# ESP32-C3_V1.net
KiCad netlist of a schematic drawn in Altium Designer
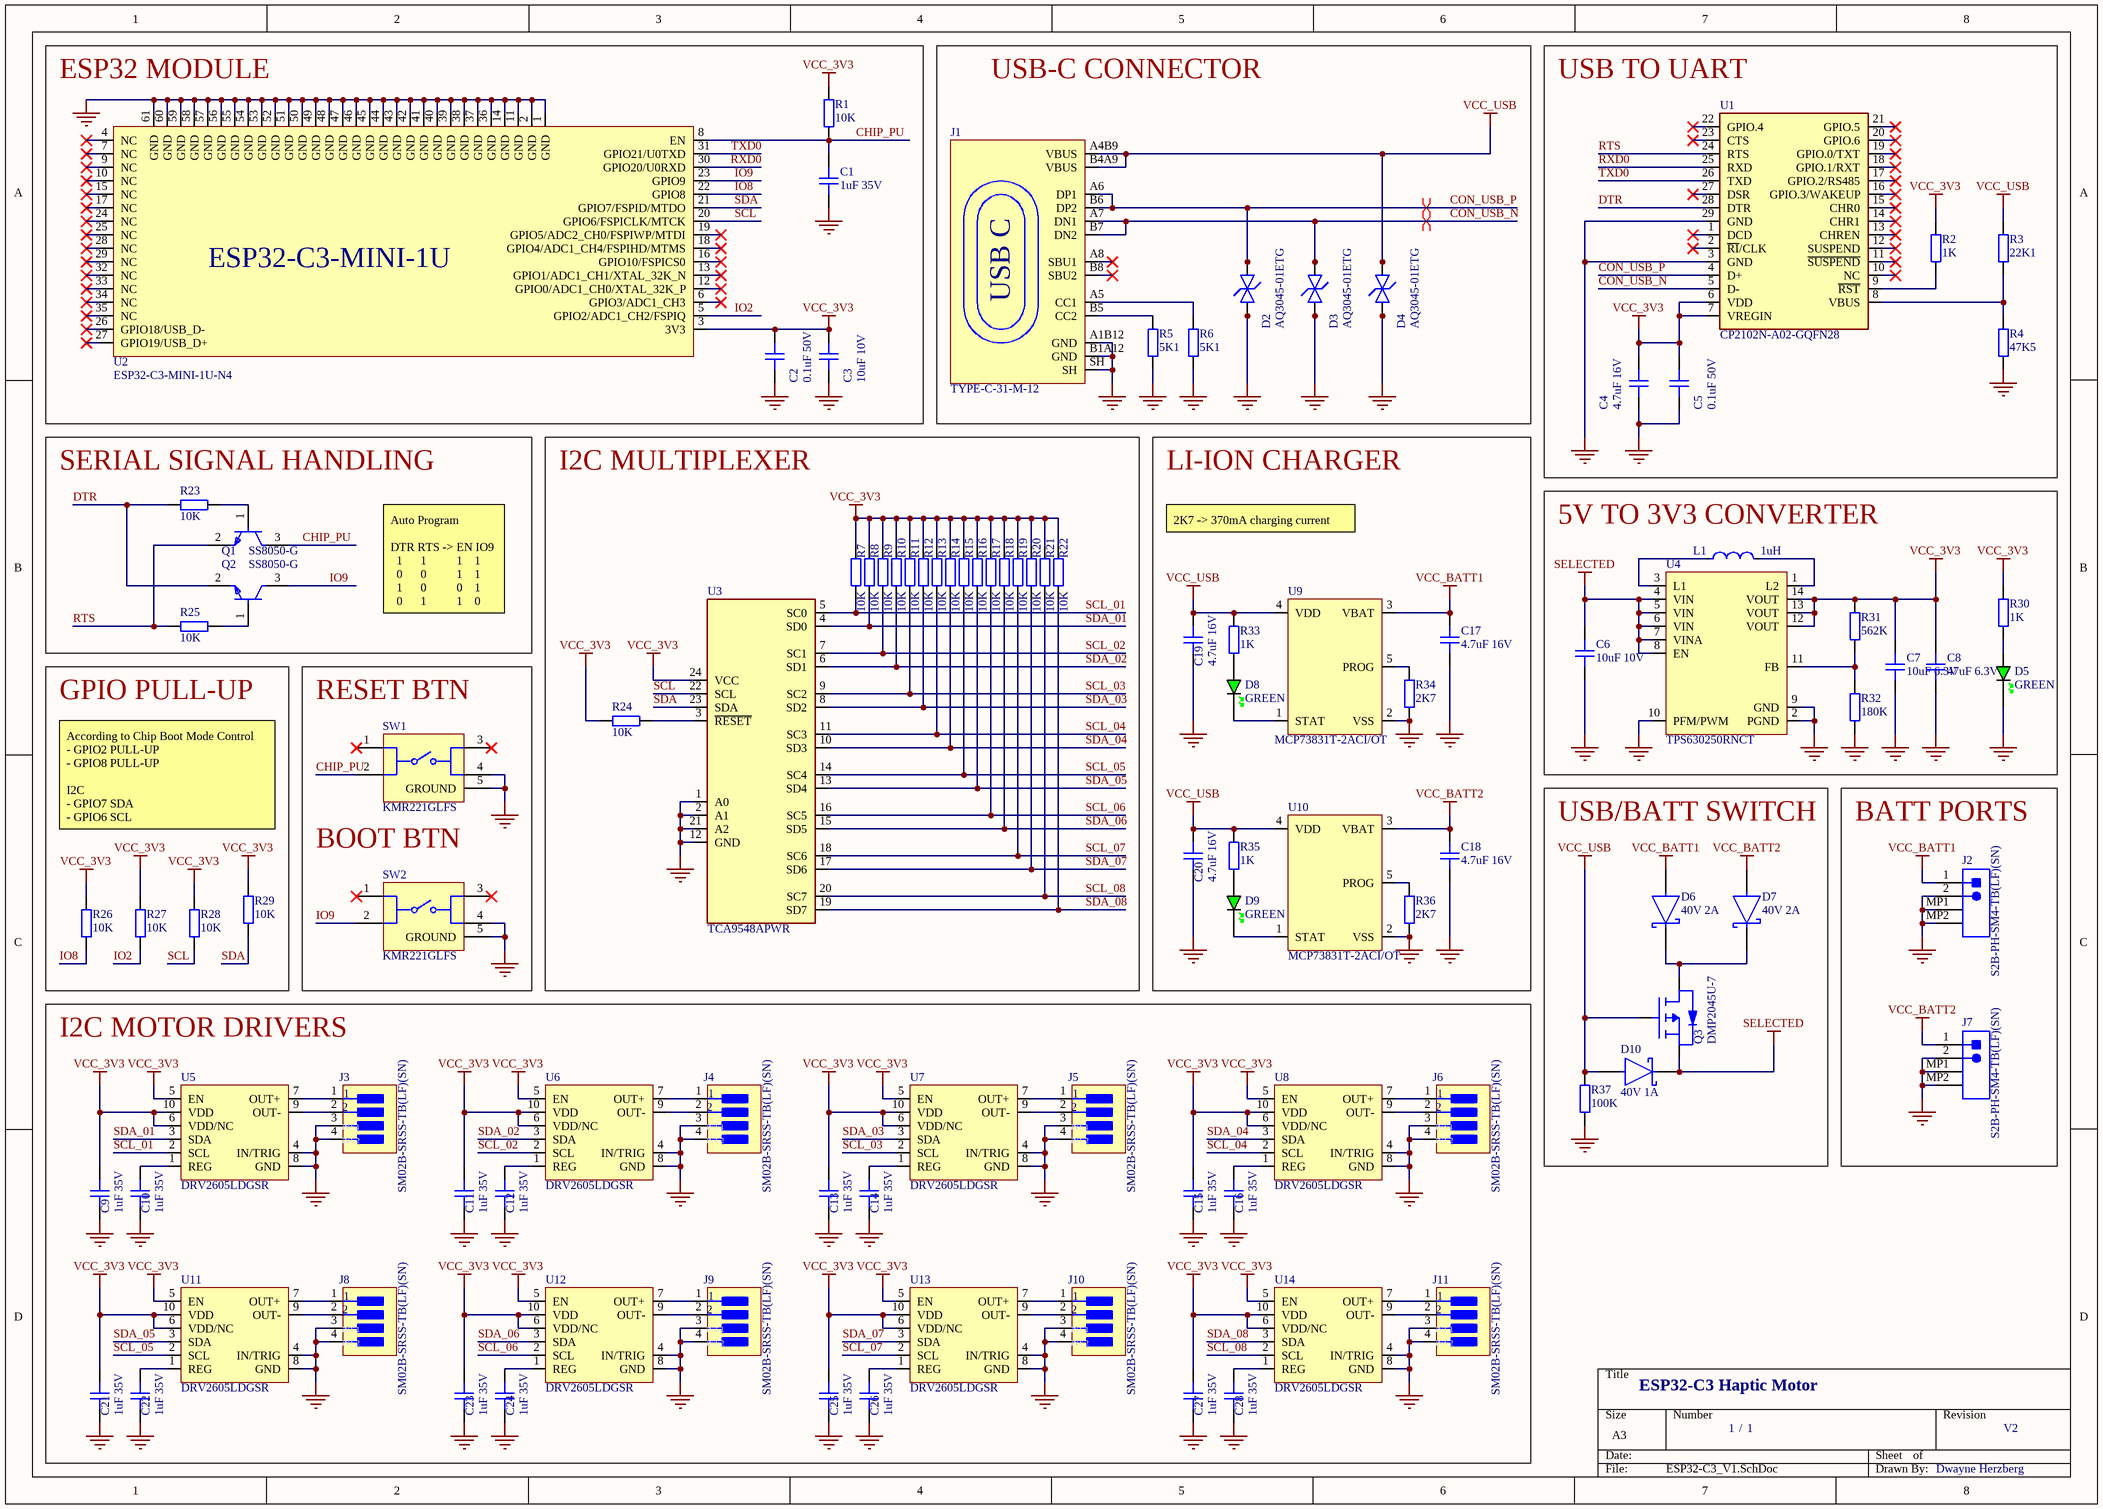
[diagram p0: ESP32-C3_V1.SchDoc]

(export (version "E")
  (design (tool "Eeschema 10.0.6"))
  (components
    (comp (ref "C1")
      (value "1uF 35V")
      (footprint "CAP_0402")
      (description "CAP CER 1UF 35V X5R 0402")
      (fields
        (field (name "MANUFACTURER") "Samsung")
        (field (name "MANUFACTURER PART NUMBER") "CL05A105KL5NRNC")
      )
      (libsource (lib "ESP32-C3") (part "CL05A105KL5NRNC"))
    )
    (comp (ref "C2")
      (value "0.1uF 50V")
      (footprint "CAP_0402")
      (description "CAP CER 0.1UF 50V X7R 0402")
      (fields
        (field (name "MANUFACTURER") "Samsung")
        (field (name "MANUFACTURER PART NUMBER") "CL05B104KB54PNC")
      )
      (libsource (lib "ESP32-C3") (part "CL05B104KB54PNC"))
    )
    (comp (ref "C3")
      (value "10uF 10V")
      (footprint "CAP_0402")
      (description "CAP CER 10UF 10V X5R 0402")
      (fields
        (field (name "MANUFACTURER") "Samsung")
        (field (name "MANUFACTURER PART NUMBER") "CL05A106MP8NUB8")
      )
      (libsource (lib "ESP32-C3") (part "CL05A106MP8NUB8"))
    )
    (comp (ref "C4")
      (value "4.7uF 16V")
      (footprint "CAP_0402")
      (description "CAP CER 4.7UF 16V X5R 0402")
      (fields
        (field (name "MANUFACTURER") "Samsung")
        (field (name "MANUFACTURER PART NUMBER") "CL05A475MO5NUNC")
      )
      (libsource (lib "ESP32-C3") (part "CL05A475MO5NUNC"))
    )
    (comp (ref "C5")
      (value "0.1uF 50V")
      (footprint "CAP_0402")
      (description "CAP CER 0.1UF 50V X7R 0402")
      (fields
        (field (name "MANUFACTURER") "Samsung")
        (field (name "MANUFACTURER PART NUMBER") "CL05B104KB54PNC")
      )
      (libsource (lib "ESP32-C3") (part "CL05B104KB54PNC"))
    )
    (comp (ref "C6")
      (value "10uF 10V")
      (footprint "CAP_0603")
      (description "CAP CER 10UF 10V X5R 0603")
      (fields
        (field (name "MANUFACTURER") "Samsung")
        (field (name "MANUFACTURER PART NUMBER") "CL10A106KP8NNNC")
      )
      (libsource (lib "ESP32-C3") (part "CL10A106KP8NNNC"))
    )
    (comp (ref "C7")
      (value "10uF 6.3V")
      (footprint "CAP_0603")
      (description "CAP CER 10UF 6.3V X5R 0603")
      (fields
        (field (name "MANUFACTURER") "Murata")
        (field (name "MANUFACTURER PART NUMBER") "GRM188R60J106ME47D")
      )
      (libsource (lib "ESP32-C3") (part "GRM188R60J106ME47D"))
    )
    (comp (ref "C8")
      (value "47uF 6.3V")
      (footprint "CAP_0805")
      (description "CAP CER 47UF 6.3V X5R 0805")
      (fields
        (field (name "MANUFACTURER") "Samsung")
        (field (name "MANUFACTURER PART NUMBER") "CL21A476MQYNNNE")
      )
      (libsource (lib "ESP32-C3") (part "CL21A476MQYNNNE"))
    )
    (comp (ref "C9")
      (value "1uF 35V")
      (footprint "CAP_0402")
      (description "CAP CER 1UF 35V X5R 0402")
      (fields
        (field (name "MANUFACTURER") "Samsung")
        (field (name "MANUFACTURER PART NUMBER") "CL05A105KL5NRNC")
      )
      (libsource (lib "ESP32-C3") (part "CL05A105KL5NRNC"))
    )
    (comp (ref "C10")
      (value "1uF 35V")
      (footprint "CAP_0402")
      (description "CAP CER 1UF 35V X5R 0402")
      (fields
        (field (name "MANUFACTURER") "Samsung")
        (field (name "MANUFACTURER PART NUMBER") "CL05A105KL5NRNC")
      )
      (libsource (lib "ESP32-C3") (part "CL05A105KL5NRNC"))
    )
    (comp (ref "C11")
      (value "1uF 35V")
      (footprint "CAP_0402")
      (description "CAP CER 1UF 35V X5R 0402")
      (fields
        (field (name "MANUFACTURER") "Samsung")
        (field (name "MANUFACTURER PART NUMBER") "CL05A105KL5NRNC")
      )
      (libsource (lib "ESP32-C3") (part "CL05A105KL5NRNC"))
    )
    (comp (ref "C12")
      (value "1uF 35V")
      (footprint "CAP_0402")
      (description "CAP CER 1UF 35V X5R 0402")
      (fields
        (field (name "MANUFACTURER") "Samsung")
        (field (name "MANUFACTURER PART NUMBER") "CL05A105KL5NRNC")
      )
      (libsource (lib "ESP32-C3") (part "CL05A105KL5NRNC"))
    )
    (comp (ref "C13")
      (value "1uF 35V")
      (footprint "CAP_0402")
      (description "CAP CER 1UF 35V X5R 0402")
      (fields
        (field (name "MANUFACTURER") "Samsung")
        (field (name "MANUFACTURER PART NUMBER") "CL05A105KL5NRNC")
      )
      (libsource (lib "ESP32-C3") (part "CL05A105KL5NRNC"))
    )
    (comp (ref "C14")
      (value "1uF 35V")
      (footprint "CAP_0402")
      (description "CAP CER 1UF 35V X5R 0402")
      (fields
        (field (name "MANUFACTURER") "Samsung")
        (field (name "MANUFACTURER PART NUMBER") "CL05A105KL5NRNC")
      )
      (libsource (lib "ESP32-C3") (part "CL05A105KL5NRNC"))
    )
    (comp (ref "C15")
      (value "1uF 35V")
      (footprint "CAP_0402")
      (description "CAP CER 1UF 35V X5R 0402")
      (fields
        (field (name "MANUFACTURER") "Samsung")
        (field (name "MANUFACTURER PART NUMBER") "CL05A105KL5NRNC")
      )
      (libsource (lib "ESP32-C3") (part "CL05A105KL5NRNC"))
    )
    (comp (ref "C16")
      (value "1uF 35V")
      (footprint "CAP_0402")
      (description "CAP CER 1UF 35V X5R 0402")
      (fields
        (field (name "MANUFACTURER") "Samsung")
        (field (name "MANUFACTURER PART NUMBER") "CL05A105KL5NRNC")
      )
      (libsource (lib "ESP32-C3") (part "CL05A105KL5NRNC"))
    )
    (comp (ref "C17")
      (value "4.7uF 16V")
      (footprint "CAP_0402")
      (description "CAP CER 4.7UF 16V X5R 0402")
      (fields
        (field (name "MANUFACTURER") "Samsung")
        (field (name "MANUFACTURER PART NUMBER") "CL05A475MO5NUNC")
      )
      (libsource (lib "ESP32-C3") (part "CL05A475MO5NUNC"))
    )
    (comp (ref "C18")
      (value "4.7uF 16V")
      (footprint "CAP_0402")
      (description "CAP CER 4.7UF 16V X5R 0402")
      (fields
        (field (name "MANUFACTURER") "Samsung")
        (field (name "MANUFACTURER PART NUMBER") "CL05A475MO5NUNC")
      )
      (libsource (lib "ESP32-C3") (part "CL05A475MO5NUNC"))
    )
    (comp (ref "C19")
      (value "4.7uF 16V")
      (footprint "CAP_0402")
      (description "CAP CER 4.7UF 16V X5R 0402")
      (fields
        (field (name "MANUFACTURER") "Samsung")
        (field (name "MANUFACTURER PART NUMBER") "CL05A475MO5NUNC")
      )
      (libsource (lib "ESP32-C3") (part "CL05A475MO5NUNC"))
    )
    (comp (ref "C20")
      (value "4.7uF 16V")
      (footprint "CAP_0402")
      (description "CAP CER 4.7UF 16V X5R 0402")
      (fields
        (field (name "MANUFACTURER") "Samsung")
        (field (name "MANUFACTURER PART NUMBER") "CL05A475MO5NUNC")
      )
      (libsource (lib "ESP32-C3") (part "CL05A475MO5NUNC"))
    )
    (comp (ref "C21")
      (value "1uF 35V")
      (footprint "CAP_0402")
      (description "CAP CER 1UF 35V X5R 0402")
      (fields
        (field (name "MANUFACTURER") "Samsung")
        (field (name "MANUFACTURER PART NUMBER") "CL05A105KL5NRNC")
      )
      (libsource (lib "ESP32-C3") (part "CL05A105KL5NRNC"))
    )
    (comp (ref "C22")
      (value "1uF 35V")
      (footprint "CAP_0402")
      (description "CAP CER 1UF 35V X5R 0402")
      (fields
        (field (name "MANUFACTURER") "Samsung")
        (field (name "MANUFACTURER PART NUMBER") "CL05A105KL5NRNC")
      )
      (libsource (lib "ESP32-C3") (part "CL05A105KL5NRNC"))
    )
    (comp (ref "C23")
      (value "1uF 35V")
      (footprint "CAP_0402")
      (description "CAP CER 1UF 35V X5R 0402")
      (fields
        (field (name "MANUFACTURER") "Samsung")
        (field (name "MANUFACTURER PART NUMBER") "CL05A105KL5NRNC")
      )
      (libsource (lib "ESP32-C3") (part "CL05A105KL5NRNC"))
    )
    (comp (ref "C24")
      (value "1uF 35V")
      (footprint "CAP_0402")
      (description "CAP CER 1UF 35V X5R 0402")
      (fields
        (field (name "MANUFACTURER") "Samsung")
        (field (name "MANUFACTURER PART NUMBER") "CL05A105KL5NRNC")
      )
      (libsource (lib "ESP32-C3") (part "CL05A105KL5NRNC"))
    )
    (comp (ref "C25")
      (value "1uF 35V")
      (footprint "CAP_0402")
      (description "CAP CER 1UF 35V X5R 0402")
      (fields
        (field (name "MANUFACTURER") "Samsung")
        (field (name "MANUFACTURER PART NUMBER") "CL05A105KL5NRNC")
      )
      (libsource (lib "ESP32-C3") (part "CL05A105KL5NRNC"))
    )
    (comp (ref "C26")
      (value "1uF 35V")
      (footprint "CAP_0402")
      (description "CAP CER 1UF 35V X5R 0402")
      (fields
        (field (name "MANUFACTURER") "Samsung")
        (field (name "MANUFACTURER PART NUMBER") "CL05A105KL5NRNC")
      )
      (libsource (lib "ESP32-C3") (part "CL05A105KL5NRNC"))
    )
    (comp (ref "C27")
      (value "1uF 35V")
      (footprint "CAP_0402")
      (description "CAP CER 1UF 35V X5R 0402")
      (fields
        (field (name "MANUFACTURER") "Samsung")
        (field (name "MANUFACTURER PART NUMBER") "CL05A105KL5NRNC")
      )
      (libsource (lib "ESP32-C3") (part "CL05A105KL5NRNC"))
    )
    (comp (ref "C28")
      (value "1uF 35V")
      (footprint "CAP_0402")
      (description "CAP CER 1UF 35V X5R 0402")
      (fields
        (field (name "MANUFACTURER") "Samsung")
        (field (name "MANUFACTURER PART NUMBER") "CL05A105KL5NRNC")
      )
      (libsource (lib "ESP32-C3") (part "CL05A105KL5NRNC"))
    )
    (comp (ref "D2")
      (value "AQ3045-01ETG")
      (footprint "SP353001ETG")
      (description "TVS DIODE 5.3VWM 12VC SOD882")
      (fields (field (name "MANUFACTURER") "Littelfuse") (field (name "JLCPCB PART") "C3710326"))
      (libsource (lib "ESP32-C3") (part "AQ3045-01ETG"))
    )
    (comp (ref "D3")
      (value "AQ3045-01ETG")
      (footprint "SP353001ETG")
      (description "TVS DIODE 5.3VWM 12VC SOD882")
      (fields (field (name "MANUFACTURER") "Littelfuse") (field (name "JLCPCB PART") "C3710326"))
      (libsource (lib "ESP32-C3") (part "AQ3045-01ETG"))
    )
    (comp (ref "D4")
      (value "AQ3045-01ETG")
      (footprint "SP353001ETG")
      (description "TVS DIODE 5.3VWM 12VC SOD882")
      (fields (field (name "MANUFACTURER") "Littelfuse") (field (name "JLCPCB PART") "C3710326"))
      (libsource (lib "ESP32-C3") (part "AQ3045-01ETG"))
    )
    (comp (ref "D5")
      (value "GREEN")
      (footprint "LED_0603_GREEN")
      (description "LED GREEN CLEAR 0603 SMD")
      (fields
        (field (name "MANUFACTURER") "Wurth Electronics")
        (field (name "MANUFACTURER PART NUMBER") "150060GS75000")
      )
      (libsource (lib "ESP32-C3") (part "150060GS75000"))
    )
    (comp (ref "D6")
      (value "40V 2A")
      (footprint "FP-DO-214AC-MFG")
      (description "DIODE SCHOTTKY 40V 2A DO214AC")
      (fields
        (field (name "MANUFACTURER") "Comchip")
        (field (name "MANUFACTURER PART NUMBER") "CDBA240LL-HF")
      )
      (libsource (lib "ESP32-C3") (part "CDBA240LL-HF"))
    )
    (comp (ref "D7")
      (value "40V 2A")
      (footprint "FP-DO-214AC-MFG")
      (description "DIODE SCHOTTKY 40V 2A DO214AC")
      (fields
        (field (name "MANUFACTURER") "Comchip")
        (field (name "MANUFACTURER PART NUMBER") "CDBA240LL-HF")
      )
      (libsource (lib "ESP32-C3") (part "CDBA240LL-HF"))
    )
    (comp (ref "D8")
      (value "GREEN")
      (footprint "LED_0603_GREEN")
      (description "LED GREEN CLEAR 0603 SMD")
      (fields
        (field (name "MANUFACTURER") "Wurth Electronics")
        (field (name "MANUFACTURER PART NUMBER") "150060GS75000")
      )
      (libsource (lib "ESP32-C3") (part "150060GS75000"))
    )
    (comp (ref "D9")
      (value "GREEN")
      (footprint "LED_0603_GREEN")
      (description "LED GREEN CLEAR 0603 SMD")
      (fields
        (field (name "MANUFACTURER") "Wurth Electronics")
        (field (name "MANUFACTURER PART NUMBER") "150060GS75000")
      )
      (libsource (lib "ESP32-C3") (part "150060GS75000"))
    )
    (comp (ref "D10")
      (value "40V 1A")
      (footprint "FP-SOD123-IPC_B")
      (description "DIODE SCHOTTKY 40V 1A SOD123")
      (fields (field (name "MANUFACTURER") "Diodes") (field (name "MANUFACTURER PART NUMBER") "1N5819HW-7-F"))
      (libsource (lib "ESP32-C3") (part "1N5819HW-7-F"))
    )
    (comp (ref "J1")
      (value "TYPE-C-31-M-12")
      (footprint "TYPE-C-31-M-12")
      (description "USB Type C Connector Horizontal SMT")
      (fields (field (name "MANUFACTURER") "Koren Hroparts") (field (name "JLCPCB PART") "C165948"))
      (libsource (lib "ESP32-C3") (part "TYPE-C-31-M-12"))
    )
    (comp (ref "J2")
      (value "S2B-PH-SM4-TB(LF)(SN)")
      (footprint "JST- S2B-PH-SM4-TB(LF)(SN)-2_V")
      (description "Male Header, Pitch 2 mm, 1 x 2 Position, Height 5.5 mm, -25 to 85 degC, RoHS, Tape and Reel")
      (fields (field (name "JLCPCB PART") "C295747"))
      (libsource (lib "ESP32-C3") (part "CMP-1755-00001-1"))
    )
    (comp (ref "J3")
      (value "SM02B-SRSS-TB(LF)(SN)")
      (footprint "FP-SM02B-SRSS-TB_LF_SN-MFG")
      (description "CONN HEADER SMD R/A 2POS 1MM")
      (fields (field (name "MANUFACTURER") "JST") (field (name "JLCPCB PART") "C160402"))
      (libsource (lib "ESP32-C3") (part "SM02B-SRSS-TB(LF)(SN)"))
    )
    (comp (ref "J4")
      (value "SM02B-SRSS-TB(LF)(SN)")
      (footprint "FP-SM02B-SRSS-TB_LF_SN-MFG")
      (description "CONN HEADER SMD R/A 2POS 1MM")
      (fields (field (name "MANUFACTURER") "JST") (field (name "JLCPCB PART") "C160402"))
      (libsource (lib "ESP32-C3") (part "SM02B-SRSS-TB(LF)(SN)"))
    )
    (comp (ref "J5")
      (value "SM02B-SRSS-TB(LF)(SN)")
      (footprint "FP-SM02B-SRSS-TB_LF_SN-MFG")
      (description "CONN HEADER SMD R/A 2POS 1MM")
      (fields (field (name "MANUFACTURER") "JST") (field (name "JLCPCB PART") "C160402"))
      (libsource (lib "ESP32-C3") (part "SM02B-SRSS-TB(LF)(SN)"))
    )
    (comp (ref "J6")
      (value "SM02B-SRSS-TB(LF)(SN)")
      (footprint "FP-SM02B-SRSS-TB_LF_SN-MFG")
      (description "CONN HEADER SMD R/A 2POS 1MM")
      (fields (field (name "MANUFACTURER") "JST") (field (name "JLCPCB PART") "C160402"))
      (libsource (lib "ESP32-C3") (part "SM02B-SRSS-TB(LF)(SN)"))
    )
    (comp (ref "J7")
      (value "S2B-PH-SM4-TB(LF)(SN)")
      (footprint "JST- S2B-PH-SM4-TB(LF)(SN)-2_V")
      (description "Male Header, Pitch 2 mm, 1 x 2 Position, Height 5.5 mm, -25 to 85 degC, RoHS, Tape and Reel")
      (fields (field (name "JLCPCB PART") "C295747"))
      (libsource (lib "ESP32-C3") (part "CMP-1755-00001-1"))
    )
    (comp (ref "J8")
      (value "SM02B-SRSS-TB(LF)(SN)")
      (footprint "FP-SM02B-SRSS-TB_LF_SN-MFG")
      (description "CONN HEADER SMD R/A 2POS 1MM")
      (fields (field (name "MANUFACTURER") "JST") (field (name "JLCPCB PART") "C160402"))
      (libsource (lib "ESP32-C3") (part "SM02B-SRSS-TB(LF)(SN)"))
    )
    (comp (ref "J9")
      (value "SM02B-SRSS-TB(LF)(SN)")
      (footprint "FP-SM02B-SRSS-TB_LF_SN-MFG")
      (description "CONN HEADER SMD R/A 2POS 1MM")
      (fields (field (name "MANUFACTURER") "JST") (field (name "JLCPCB PART") "C160402"))
      (libsource (lib "ESP32-C3") (part "SM02B-SRSS-TB(LF)(SN)"))
    )
    (comp (ref "J10")
      (value "SM02B-SRSS-TB(LF)(SN)")
      (footprint "FP-SM02B-SRSS-TB_LF_SN-MFG")
      (description "CONN HEADER SMD R/A 2POS 1MM")
      (fields (field (name "MANUFACTURER") "JST") (field (name "JLCPCB PART") "C160402"))
      (libsource (lib "ESP32-C3") (part "SM02B-SRSS-TB(LF)(SN)"))
    )
    (comp (ref "J11")
      (value "SM02B-SRSS-TB(LF)(SN)")
      (footprint "FP-SM02B-SRSS-TB_LF_SN-MFG")
      (description "CONN HEADER SMD R/A 2POS 1MM")
      (fields (field (name "MANUFACTURER") "JST") (field (name "JLCPCB PART") "C160402"))
      (libsource (lib "ESP32-C3") (part "SM02B-SRSS-TB(LF)(SN)"))
    )
    (comp (ref "L1")
      (value "1uH")
      (footprint "FP-XAL4020-102MEC-MFG")
      (description "FIXED IND 1UH 9.6A 14.6MOHM SM")
      (fields
        (field (name "MANUFACTURER") "Coilcraft")
        (field (name "MANUFACTURER PART NUMBER") "XAL4020-102MEC")
      )
      (libsource (lib "ESP32-C3") (part "XAL4020-102MEC"))
    )
    (comp (ref "Q1")
      (value "SS8050-G")
      (footprint "FP-SS8050-G-IPC_B")
      (description "TRANS NPN 25V 1.5A SOT-23-3")
      (fields (field (name "MANUFACTURER") "Comchip") (field (name "JLCPCB PART") "C3199946"))
      (libsource (lib "ESP32-C3") (part "SS8050-G"))
    )
    (comp (ref "Q2")
      (value "SS8050-G")
      (footprint "FP-SS8050-G-IPC_B")
      (description "TRANS NPN 25V 1.5A SOT-23-3")
      (fields (field (name "MANUFACTURER") "Comchip") (field (name "JLCPCB PART") "C3199946"))
      (libsource (lib "ESP32-C3") (part "SS8050-G"))
    )
    (comp (ref "Q3")
      (value "DMP2045U-7")
      (footprint "SOT96P240X115-3N")
      (description "MOSFET P-CH 20V 4.3A SOT23")
      (fields (field (name "MANUFACTURER") "Diodes") (field (name "JLCPCB PART") "C459541"))
      (libsource (lib "ESP32-C3") (part "DMP2045U-7"))
    )
    (comp (ref "R1")
      (value "10K")
      (footprint "RES_0402")
      (description "RES SMD 10K OHM 1% 1/16W 0402")
      (fields
        (field (name "MANUFACTURER") "Yageo")
        (field (name "MANUFACTURER PART NUMBER") "AC0402FR-0710KL")
      )
      (libsource (lib "ESP32-C3") (part "AC0402FR-0710KL"))
    )
    (comp (ref "R2")
      (value "1K")
      (footprint "RES_0402")
      (description "RES 1K OHM 5% 1/16W 0402")
      (fields
        (field (name "MANUFACTURER") "Yageo")
        (field (name "MANUFACTURER PART NUMBER") "RC0402JR-071KL")
      )
      (libsource (lib "ESP32-C3") (part "RC0402JR-071KL"))
    )
    (comp (ref "R3")
      (value "22K1")
      (footprint "RES_0402")
      (description "RES 22.1K OHM 1% 1/16W 0402")
      (fields
        (field (name "MANUFACTURER") "Yageo")
        (field (name "MANUFACTURER PART NUMBER") "RC0402FR-0722K1L")
      )
      (libsource (lib "ESP32-C3") (part "RC0402FR-0722K1L"))
    )
    (comp (ref "R4")
      (value "47K5")
      (footprint "RES_0402")
      (description "RES 47.5K OHM 1% 1/16W 0402")
      (fields
        (field (name "MANUFACTURER") "Yageo")
        (field (name "MANUFACTURER PART NUMBER") "RC0402FR-0747K5L")
      )
      (libsource (lib "ESP32-C3") (part "RC0402FR-0747K5L"))
    )
    (comp (ref "R5")
      (value "5K1")
      (footprint "RES_0402")
      (description "RES SMD 5.1K OHM 1% 1/16W 0402")
      (fields
        (field (name "MANUFACTURER") "Yageo")
        (field (name "MANUFACTURER PART NUMBER") "AC0402FR-075K1L")
      )
      (libsource (lib "ESP32-C3") (part "AC0402FR-075K1L"))
    )
    (comp (ref "R6")
      (value "5K1")
      (footprint "RES_0402")
      (description "RES SMD 5.1K OHM 1% 1/16W 0402")
      (fields
        (field (name "MANUFACTURER") "Yageo")
        (field (name "MANUFACTURER PART NUMBER") "AC0402FR-075K1L")
      )
      (libsource (lib "ESP32-C3") (part "AC0402FR-075K1L"))
    )
    (comp (ref "R7")
      (value "10K")
      (footprint "RES_0402")
      (description "RES SMD 10K OHM 1% 1/16W 0402")
      (fields
        (field (name "MANUFACTURER") "Yageo")
        (field (name "MANUFACTURER PART NUMBER") "AC0402FR-0710KL")
      )
      (libsource (lib "ESP32-C3") (part "AC0402FR-0710KL"))
    )
    (comp (ref "R8")
      (value "10K")
      (footprint "RES_0402")
      (description "RES SMD 10K OHM 1% 1/16W 0402")
      (fields
        (field (name "MANUFACTURER") "Yageo")
        (field (name "MANUFACTURER PART NUMBER") "AC0402FR-0710KL")
      )
      (libsource (lib "ESP32-C3") (part "AC0402FR-0710KL"))
    )
    (comp (ref "R9")
      (value "10K")
      (footprint "RES_0402")
      (description "RES SMD 10K OHM 1% 1/16W 0402")
      (fields
        (field (name "MANUFACTURER") "Yageo")
        (field (name "MANUFACTURER PART NUMBER") "AC0402FR-0710KL")
      )
      (libsource (lib "ESP32-C3") (part "AC0402FR-0710KL"))
    )
    (comp (ref "R10")
      (value "10K")
      (footprint "RES_0402")
      (description "RES SMD 10K OHM 1% 1/16W 0402")
      (fields
        (field (name "MANUFACTURER") "Yageo")
        (field (name "MANUFACTURER PART NUMBER") "AC0402FR-0710KL")
      )
      (libsource (lib "ESP32-C3") (part "AC0402FR-0710KL"))
    )
    (comp (ref "R11")
      (value "10K")
      (footprint "RES_0402")
      (description "RES SMD 10K OHM 1% 1/16W 0402")
      (fields
        (field (name "MANUFACTURER") "Yageo")
        (field (name "MANUFACTURER PART NUMBER") "AC0402FR-0710KL")
      )
      (libsource (lib "ESP32-C3") (part "AC0402FR-0710KL"))
    )
    (comp (ref "R12")
      (value "10K")
      (footprint "RES_0402")
      (description "RES SMD 10K OHM 1% 1/16W 0402")
      (fields
        (field (name "MANUFACTURER") "Yageo")
        (field (name "MANUFACTURER PART NUMBER") "AC0402FR-0710KL")
      )
      (libsource (lib "ESP32-C3") (part "AC0402FR-0710KL"))
    )
    (comp (ref "R13")
      (value "10K")
      (footprint "RES_0402")
      (description "RES SMD 10K OHM 1% 1/16W 0402")
      (fields
        (field (name "MANUFACTURER") "Yageo")
        (field (name "MANUFACTURER PART NUMBER") "AC0402FR-0710KL")
      )
      (libsource (lib "ESP32-C3") (part "AC0402FR-0710KL"))
    )
    (comp (ref "R14")
      (value "10K")
      (footprint "RES_0402")
      (description "RES SMD 10K OHM 1% 1/16W 0402")
      (fields
        (field (name "MANUFACTURER") "Yageo")
        (field (name "MANUFACTURER PART NUMBER") "AC0402FR-0710KL")
      )
      (libsource (lib "ESP32-C3") (part "AC0402FR-0710KL"))
    )
    (comp (ref "R15")
      (value "10K")
      (footprint "RES_0402")
      (description "RES SMD 10K OHM 1% 1/16W 0402")
      (fields
        (field (name "MANUFACTURER") "Yageo")
        (field (name "MANUFACTURER PART NUMBER") "AC0402FR-0710KL")
      )
      (libsource (lib "ESP32-C3") (part "AC0402FR-0710KL"))
    )
    (comp (ref "R16")
      (value "10K")
      (footprint "RES_0402")
      (description "RES SMD 10K OHM 1% 1/16W 0402")
      (fields
        (field (name "MANUFACTURER") "Yageo")
        (field (name "MANUFACTURER PART NUMBER") "AC0402FR-0710KL")
      )
      (libsource (lib "ESP32-C3") (part "AC0402FR-0710KL"))
    )
    (comp (ref "R17")
      (value "10K")
      (footprint "RES_0402")
      (description "RES SMD 10K OHM 1% 1/16W 0402")
      (fields
        (field (name "MANUFACTURER") "Yageo")
        (field (name "MANUFACTURER PART NUMBER") "AC0402FR-0710KL")
      )
      (libsource (lib "ESP32-C3") (part "AC0402FR-0710KL"))
    )
    (comp (ref "R18")
      (value "10K")
      (footprint "RES_0402")
      (description "RES SMD 10K OHM 1% 1/16W 0402")
      (fields
        (field (name "MANUFACTURER") "Yageo")
        (field (name "MANUFACTURER PART NUMBER") "AC0402FR-0710KL")
      )
      (libsource (lib "ESP32-C3") (part "AC0402FR-0710KL"))
    )
    (comp (ref "R19")
      (value "10K")
      (footprint "RES_0402")
      (description "RES SMD 10K OHM 1% 1/16W 0402")
      (fields
        (field (name "MANUFACTURER") "Yageo")
        (field (name "MANUFACTURER PART NUMBER") "AC0402FR-0710KL")
      )
      (libsource (lib "ESP32-C3") (part "AC0402FR-0710KL"))
    )
    (comp (ref "R20")
      (value "10K")
      (footprint "RES_0402")
      (description "RES SMD 10K OHM 1% 1/16W 0402")
      (fields
        (field (name "MANUFACTURER") "Yageo")
        (field (name "MANUFACTURER PART NUMBER") "AC0402FR-0710KL")
      )
      (libsource (lib "ESP32-C3") (part "AC0402FR-0710KL"))
    )
    (comp (ref "R21")
      (value "10K")
      (footprint "RES_0402")
      (description "RES SMD 10K OHM 1% 1/16W 0402")
      (fields
        (field (name "MANUFACTURER") "Yageo")
        (field (name "MANUFACTURER PART NUMBER") "AC0402FR-0710KL")
      )
      (libsource (lib "ESP32-C3") (part "AC0402FR-0710KL"))
    )
    (comp (ref "R22")
      (value "10K")
      (footprint "RES_0402")
      (description "RES SMD 10K OHM 1% 1/16W 0402")
      (fields
        (field (name "MANUFACTURER") "Yageo")
        (field (name "MANUFACTURER PART NUMBER") "AC0402FR-0710KL")
      )
      (libsource (lib "ESP32-C3") (part "AC0402FR-0710KL"))
    )
    (comp (ref "R23")
      (value "10K")
      (footprint "RES_0402")
      (description "RES SMD 10K OHM 1% 1/16W 0402")
      (fields
        (field (name "MANUFACTURER") "Yageo")
        (field (name "MANUFACTURER PART NUMBER") "AC0402FR-0710KL")
      )
      (libsource (lib "ESP32-C3") (part "AC0402FR-0710KL"))
    )
    (comp (ref "R24")
      (value "10K")
      (footprint "RES_0402")
      (description "RES SMD 10K OHM 1% 1/16W 0402")
      (fields
        (field (name "MANUFACTURER") "Yageo")
        (field (name "MANUFACTURER PART NUMBER") "AC0402FR-0710KL")
      )
      (libsource (lib "ESP32-C3") (part "AC0402FR-0710KL"))
    )
    (comp (ref "R25")
      (value "10K")
      (footprint "RES_0402")
      (description "RES SMD 10K OHM 1% 1/16W 0402")
      (fields
        (field (name "MANUFACTURER") "Yageo")
        (field (name "MANUFACTURER PART NUMBER") "AC0402FR-0710KL")
      )
      (libsource (lib "ESP32-C3") (part "AC0402FR-0710KL"))
    )
    (comp (ref "R26")
      (value "10K")
      (footprint "RES_0402")
      (description "RES SMD 10K OHM 1% 1/16W 0402")
      (fields
        (field (name "MANUFACTURER") "Yageo")
        (field (name "MANUFACTURER PART NUMBER") "AC0402FR-0710KL")
      )
      (libsource (lib "ESP32-C3") (part "AC0402FR-0710KL"))
    )
    (comp (ref "R27")
      (value "10K")
      (footprint "RES_0402")
      (description "RES SMD 10K OHM 1% 1/16W 0402")
      (fields
        (field (name "MANUFACTURER") "Yageo")
        (field (name "MANUFACTURER PART NUMBER") "AC0402FR-0710KL")
      )
      (libsource (lib "ESP32-C3") (part "AC0402FR-0710KL"))
    )
    (comp (ref "R28")
      (value "10K")
      (footprint "RES_0402")
      (description "RES SMD 10K OHM 1% 1/16W 0402")
      (fields
        (field (name "MANUFACTURER") "Yageo")
        (field (name "MANUFACTURER PART NUMBER") "AC0402FR-0710KL")
      )
      (libsource (lib "ESP32-C3") (part "AC0402FR-0710KL"))
    )
    (comp (ref "R29")
      (value "10K")
      (footprint "RES_0402")
      (description "RES SMD 10K OHM 1% 1/16W 0402")
      (fields
        (field (name "MANUFACTURER") "Yageo")
        (field (name "MANUFACTURER PART NUMBER") "AC0402FR-0710KL")
      )
      (libsource (lib "ESP32-C3") (part "AC0402FR-0710KL"))
    )
    (comp (ref "R30")
      (value "1K")
      (footprint "RES_0402")
      (description "RES 1K OHM 5% 1/16W 0402")
      (fields
        (field (name "MANUFACTURER") "Yageo")
        (field (name "MANUFACTURER PART NUMBER") "RC0402JR-071KL")
      )
      (libsource (lib "ESP32-C3") (part "RC0402JR-071KL"))
    )
    (comp (ref "R31")
      (value "562K")
      (footprint "RES_0603")
      (description "RES SMD 562K OHM 1% 1/10W 0603")
      (fields
        (field (name "MANUFACTURER") "Yageo")
        (field (name "MANUFACTURER PART NUMBER") "AC0603FR-07562KL")
      )
      (libsource (lib "ESP32-C3") (part "AC0603FR-07562KL"))
    )
    (comp (ref "R32")
      (value "180K")
      (footprint "RES_0603")
      (description "RES 180K OHM 1% 1/10W 0603")
      (fields
        (field (name "MANUFACTURER") "Yageo")
        (field (name "MANUFACTURER PART NUMBER") "RC0603FR-07180KL")
      )
      (libsource (lib "ESP32-C3") (part "RC0603FR-07180KL"))
    )
    (comp (ref "R33")
      (value "1K")
      (footprint "RES_0402")
      (description "RES 1K OHM 5% 1/16W 0402")
      (fields
        (field (name "MANUFACTURER") "Yageo")
        (field (name "MANUFACTURER PART NUMBER") "RC0402JR-071KL")
      )
      (libsource (lib "ESP32-C3") (part "RC0402JR-071KL"))
    )
    (comp (ref "R34")
      (value "2K7")
      (footprint "RES_0402")
      (description "RES 2.7K OHM 1% 1/16W 0402")
      (fields
        (field (name "MANUFACTURER") "Yageo")
        (field (name "MANUFACTURER PART NUMBER") "RC0402FR-072K7L")
      )
      (libsource (lib "ESP32-C3") (part "RC0402FR-072K7L"))
    )
    (comp (ref "R35")
      (value "1K")
      (footprint "RES_0402")
      (description "RES 1K OHM 5% 1/16W 0402")
      (fields
        (field (name "MANUFACTURER") "Yageo")
        (field (name "MANUFACTURER PART NUMBER") "RC0402JR-071KL")
      )
      (libsource (lib "ESP32-C3") (part "RC0402JR-071KL"))
    )
    (comp (ref "R36")
      (value "2K7")
      (footprint "RES_0402")
      (description "RES 2.7K OHM 1% 1/16W 0402")
      (fields
        (field (name "MANUFACTURER") "Yageo")
        (field (name "MANUFACTURER PART NUMBER") "RC0402FR-072K7L")
      )
      (libsource (lib "ESP32-C3") (part "RC0402FR-072K7L"))
    )
    (comp (ref "R37")
      (value "100K")
      (footprint "RES_0402")
      (description "RES 100K OHM 1% 1/16W 0402")
      (fields
        (field (name "MANUFACTURER") "Yageo")
        (field (name "MANUFACTURER PART NUMBER") "RC0402FR-07100KL")
      )
      (libsource (lib "ESP32-C3") (part "RC0402FR-07100KL"))
    )
    (comp (ref "SW1")
      (value "KMR221GLFS")
      (footprint "FP-KMR221GLFS-MFG")
      (description "SWITCH TACTILE SPST-NO 0.05A 32V")
      (fields (field (name "MANUFACTURER") "ITT C&K") (field (name "JLCPCB PART") "C72443"))
      (libsource (lib "ESP32-C3") (part "KMR221GLFS"))
    )
    (comp (ref "SW2")
      (value "KMR221GLFS")
      (footprint "FP-KMR221GLFS-MFG")
      (description "SWITCH TACTILE SPST-NO 0.05A 32V")
      (fields (field (name "MANUFACTURER") "ITT C&K") (field (name "JLCPCB PART") "C72443"))
      (libsource (lib "ESP32-C3") (part "KMR221GLFS"))
    )
    (comp (ref "U1")
      (value "CP2102N-A02-GQFN28")
      (footprint "FP-CP2102N-A02-GQFN28-IPC_B")
      (description "IC USB TO UART BRIDGE QFN28")
      (fields (field (name "MANUFACTURER") "Silicon Labs") (field (name "JLCPCB PART") "C1550553"))
      (libsource (lib "ESP32-C3") (part "CP2102N-A02-GQFN28"))
    )
    (comp (ref "U2")
      (value "ESP32-C3-MINI-1U-N4")
      (footprint "ESP32-C3-MINI-1U_EXP")
      (description "RF TXRX MOD BT WIFIU.FL SMD")
      (fields (field (name "MANUFACTURER") "Espressif Systems") (field (name "JLCPCB PART") "C2911374"))
      (libsource (lib "ESP32-C3") (part "ESP32-C3-MINI-1U-N4"))
    )
    (comp (ref "U3")
      (value "TCA9548APWR")
      (footprint "FP-PW0024A-IPC_B")
      (description "IC BUS SWITCH 1 X 8:1 24TSSOP")
      (fields (field (name "MANUFACTURER") "Texas Instruments") (field (name "JLCPCB PART") "C130026"))
      (libsource (lib "ESP32-C3") (part "TCA9548APWR"))
    )
    (comp (ref "U4")
      (value "TPS630250RNCT")
      (footprint "FP-RNC0014A-MFG")
      (description "IC REG BCK BST ADJ 2A/4A 14VQFN")
      (fields (field (name "MANUFACTURER") "Texas Instruments") (field (name "JLCPCB PART") "C2070882"))
      (libsource (lib "ESP32-C3") (part "TPS630250RNCT"))
    )
    (comp (ref "U5")
      (value "DRV2605LDGSR")
      (footprint "FP-DGS0010A-IPC_B")
      (description "IC MOTOR DRIVER 2V-5.5V 10VSSOP")
      (fields (field (name "MANUFACTURER") "Texas Instruments") (field (name "JLCPCB PART") "C527464"))
      (libsource (lib "ESP32-C3") (part "DRV2605LDGSR"))
    )
    (comp (ref "U6")
      (value "DRV2605LDGSR")
      (footprint "FP-DGS0010A-IPC_B")
      (description "IC MOTOR DRIVER 2V-5.5V 10VSSOP")
      (fields (field (name "MANUFACTURER") "Texas Instruments") (field (name "JLCPCB PART") "C527464"))
      (libsource (lib "ESP32-C3") (part "DRV2605LDGSR"))
    )
    (comp (ref "U7")
      (value "DRV2605LDGSR")
      (footprint "FP-DGS0010A-IPC_B")
      (description "IC MOTOR DRIVER 2V-5.5V 10VSSOP")
      (fields (field (name "MANUFACTURER") "Texas Instruments") (field (name "JLCPCB PART") "C527464"))
      (libsource (lib "ESP32-C3") (part "DRV2605LDGSR"))
    )
    (comp (ref "U8")
      (value "DRV2605LDGSR")
      (footprint "FP-DGS0010A-IPC_B")
      (description "IC MOTOR DRIVER 2V-5.5V 10VSSOP")
      (fields (field (name "MANUFACTURER") "Texas Instruments") (field (name "JLCPCB PART") "C527464"))
      (libsource (lib "ESP32-C3") (part "DRV2605LDGSR"))
    )
    (comp (ref "U9")
      (value "MCP73831T-2ACI/OT")
      (footprint "FP-C04-091-OT-IPC_B")
      (description "IC BATT CNTL LI-ION 1CEL SOT23-5")
      (fields (field (name "MANUFACTURER") "Microchip") (field (name "JLCPCB PART") "C424093"))
      (libsource (lib "ESP32-C3") (part "MCP73831T-2ACI/OT"))
    )
    (comp (ref "U10")
      (value "MCP73831T-2ACI/OT")
      (footprint "FP-C04-091-OT-IPC_B")
      (description "IC BATT CNTL LI-ION 1CEL SOT23-5")
      (fields (field (name "MANUFACTURER") "Microchip") (field (name "JLCPCB PART") "C424093"))
      (libsource (lib "ESP32-C3") (part "MCP73831T-2ACI/OT"))
    )
    (comp (ref "U11")
      (value "DRV2605LDGSR")
      (footprint "FP-DGS0010A-IPC_B")
      (description "IC MOTOR DRIVER 2V-5.5V 10VSSOP")
      (fields (field (name "MANUFACTURER") "Texas Instruments") (field (name "JLCPCB PART") "C527464"))
      (libsource (lib "ESP32-C3") (part "DRV2605LDGSR"))
    )
    (comp (ref "U12")
      (value "DRV2605LDGSR")
      (footprint "FP-DGS0010A-IPC_B")
      (description "IC MOTOR DRIVER 2V-5.5V 10VSSOP")
      (fields (field (name "MANUFACTURER") "Texas Instruments") (field (name "JLCPCB PART") "C527464"))
      (libsource (lib "ESP32-C3") (part "DRV2605LDGSR"))
    )
    (comp (ref "U13")
      (value "DRV2605LDGSR")
      (footprint "FP-DGS0010A-IPC_B")
      (description "IC MOTOR DRIVER 2V-5.5V 10VSSOP")
      (fields (field (name "MANUFACTURER") "Texas Instruments") (field (name "JLCPCB PART") "C527464"))
      (libsource (lib "ESP32-C3") (part "DRV2605LDGSR"))
    )
    (comp (ref "U14")
      (value "DRV2605LDGSR")
      (footprint "FP-DGS0010A-IPC_B")
      (description "IC MOTOR DRIVER 2V-5.5V 10VSSOP")
      (fields (field (name "MANUFACTURER") "Texas Instruments") (field (name "JLCPCB PART") "C527464"))
      (libsource (lib "ESP32-C3") (part "DRV2605LDGSR"))
    )
  )
  (nets
    (net (code "1") (name "/CHIP_PU") (class "Default")
      (node (ref "C1") (pin "2") (pinfunction "2_2") (pintype "passive"))
      (node (ref "Q1") (pin "3") (pinfunction "C_3") (pintype "passive"))
      (node (ref "R1") (pin "1") (pinfunction "1_1") (pintype "passive"))
      (node (ref "SW1") (pin "2") (pinfunction "2_2") (pintype "passive"))
      (node (ref "U2") (pin "8") (pinfunction "EN_8") (pintype "passive"))
    )
    (net (code "2") (name "/CON_USB_N") (class "Default")
      (node (ref "D3") (pin "2") (pinfunction "K_2") (pintype "passive"))
      (node (ref "D3") (pin "K") (pinfunction "K_K") (pintype "passive"))
      (node (ref "J1") (pin "A7") (pinfunction "DN1_A7") (pintype "passive"))
      (node (ref "J1") (pin "B7") (pinfunction "DN2_B7") (pintype "passive"))
      (node (ref "U1") (pin "5") (pinfunction "D-_5") (pintype "passive"))
    )
    (net (code "3") (name "/CON_USB_P") (class "Default")
      (node (ref "D2") (pin "2") (pinfunction "K_2") (pintype "passive"))
      (node (ref "D2") (pin "K") (pinfunction "K_K") (pintype "passive"))
      (node (ref "J1") (pin "A6") (pinfunction "DP1_A6") (pintype "passive"))
      (node (ref "J1") (pin "B6") (pinfunction "DP2_B6") (pintype "passive"))
      (node (ref "U1") (pin "4") (pinfunction "D+_4") (pintype "passive"))
    )
    (net (code "4") (name "/DTR") (class "Default")
      (node (ref "Q2") (pin "2") (pinfunction "E_2") (pintype "passive"))
      (node (ref "R23") (pin "2") (pinfunction "2_2") (pintype "passive"))
      (node (ref "U1") (pin "28") (pinfunction "DTR_28") (pintype "passive"))
    )
    (net (code "5") (name "/IO2") (class "Default")
      (node (ref "R27") (pin "1") (pinfunction "1_1") (pintype "passive"))
      (node (ref "U2") (pin "5") (pinfunction "GPIO2/ADC1_CH2/FSPIQ_5") (pintype "passive"))
    )
    (net (code "6") (name "/IO8") (class "Default")
      (node (ref "R26") (pin "1") (pinfunction "1_1") (pintype "passive"))
      (node (ref "U2") (pin "22") (pinfunction "GPIO8_22") (pintype "passive"))
    )
    (net (code "7") (name "/IO9") (class "Default")
      (node (ref "Q2") (pin "3") (pinfunction "C_3") (pintype "passive"))
      (node (ref "SW2") (pin "2") (pinfunction "2_2") (pintype "passive"))
      (node (ref "U2") (pin "23") (pinfunction "GPIO9_23") (pintype "passive"))
    )
    (net (code "8") (name "/RTS") (class "Default")
      (node (ref "Q1") (pin "2") (pinfunction "E_2") (pintype "passive"))
      (node (ref "R25") (pin "2") (pinfunction "2_2") (pintype "passive"))
      (node (ref "U1") (pin "24") (pinfunction "RTS_24") (pintype "passive"))
    )
    (net (code "9") (name "/RXD0") (class "Default")
      (node (ref "U1") (pin "25") (pinfunction "RXD_25") (pintype "passive"))
      (node (ref "U2") (pin "30") (pinfunction "GPIO20/U0RXD_30") (pintype "passive"))
    )
    (net (code "10") (name "/SCL") (class "Default")
      (node (ref "R28") (pin "1") (pinfunction "1_1") (pintype "passive"))
      (node (ref "U2") (pin "20") (pinfunction "GPIO6/FSPICLK/MTCK_20") (pintype "passive"))
      (node (ref "U3") (pin "22") (pinfunction "SCL_22") (pintype "passive"))
    )
    (net (code "11") (name "/SCL_01") (class "Default")
      (node (ref "R7") (pin "1") (pinfunction "1_1") (pintype "passive"))
      (node (ref "U3") (pin "5") (pinfunction "SC0_5") (pintype "passive"))
      (node (ref "U5") (pin "2") (pinfunction "SCL_2") (pintype "passive"))
    )
    (net (code "12") (name "/SCL_02") (class "Default")
      (node (ref "R9") (pin "1") (pinfunction "1_1") (pintype "passive"))
      (node (ref "U3") (pin "7") (pinfunction "SC1_7") (pintype "passive"))
      (node (ref "U6") (pin "2") (pinfunction "SCL_2") (pintype "passive"))
    )
    (net (code "13") (name "/SCL_03") (class "Default")
      (node (ref "R11") (pin "1") (pinfunction "1_1") (pintype "passive"))
      (node (ref "U3") (pin "9") (pinfunction "SC2_9") (pintype "passive"))
      (node (ref "U7") (pin "2") (pinfunction "SCL_2") (pintype "passive"))
    )
    (net (code "14") (name "/SCL_04") (class "Default")
      (node (ref "R13") (pin "1") (pinfunction "1_1") (pintype "passive"))
      (node (ref "U3") (pin "11") (pinfunction "SC3_11") (pintype "passive"))
      (node (ref "U8") (pin "2") (pinfunction "SCL_2") (pintype "passive"))
    )
    (net (code "15") (name "/SCL_05") (class "Default")
      (node (ref "R15") (pin "1") (pinfunction "1_1") (pintype "passive"))
      (node (ref "U11") (pin "2") (pinfunction "SCL_2") (pintype "passive"))
      (node (ref "U3") (pin "14") (pinfunction "SC4_14") (pintype "passive"))
    )
    (net (code "16") (name "/SCL_06") (class "Default")
      (node (ref "R17") (pin "1") (pinfunction "1_1") (pintype "passive"))
      (node (ref "U12") (pin "2") (pinfunction "SCL_2") (pintype "passive"))
      (node (ref "U3") (pin "16") (pinfunction "SC5_16") (pintype "passive"))
    )
    (net (code "17") (name "/SCL_07") (class "Default")
      (node (ref "R19") (pin "1") (pinfunction "1_1") (pintype "passive"))
      (node (ref "U13") (pin "2") (pinfunction "SCL_2") (pintype "passive"))
      (node (ref "U3") (pin "18") (pinfunction "SC6_18") (pintype "passive"))
    )
    (net (code "18") (name "/SCL_08") (class "Default")
      (node (ref "R21") (pin "1") (pinfunction "1_1") (pintype "passive"))
      (node (ref "U14") (pin "2") (pinfunction "SCL_2") (pintype "passive"))
      (node (ref "U3") (pin "20") (pinfunction "SC7_20") (pintype "passive"))
    )
    (net (code "19") (name "/SDA") (class "Default")
      (node (ref "R29") (pin "1") (pinfunction "1_1") (pintype "passive"))
      (node (ref "U2") (pin "21") (pinfunction "GPIO7/FSPID/MTDO_21") (pintype "passive"))
      (node (ref "U3") (pin "23") (pinfunction "SDA_23") (pintype "passive"))
    )
    (net (code "20") (name "/SDA_01") (class "Default")
      (node (ref "R8") (pin "1") (pinfunction "1_1") (pintype "passive"))
      (node (ref "U3") (pin "4") (pinfunction "SD0_4") (pintype "passive"))
      (node (ref "U5") (pin "3") (pinfunction "SDA_3") (pintype "passive"))
    )
    (net (code "21") (name "/SDA_02") (class "Default")
      (node (ref "R10") (pin "1") (pinfunction "1_1") (pintype "passive"))
      (node (ref "U3") (pin "6") (pinfunction "SD1_6") (pintype "passive"))
      (node (ref "U6") (pin "3") (pinfunction "SDA_3") (pintype "passive"))
    )
    (net (code "22") (name "/SDA_03") (class "Default")
      (node (ref "R12") (pin "1") (pinfunction "1_1") (pintype "passive"))
      (node (ref "U3") (pin "8") (pinfunction "SD2_8") (pintype "passive"))
      (node (ref "U7") (pin "3") (pinfunction "SDA_3") (pintype "passive"))
    )
    (net (code "23") (name "/SDA_04") (class "Default")
      (node (ref "R14") (pin "1") (pinfunction "1_1") (pintype "passive"))
      (node (ref "U3") (pin "10") (pinfunction "SD3_10") (pintype "passive"))
      (node (ref "U8") (pin "3") (pinfunction "SDA_3") (pintype "passive"))
    )
    (net (code "24") (name "/SDA_05") (class "Default")
      (node (ref "R16") (pin "1") (pinfunction "1_1") (pintype "passive"))
      (node (ref "U11") (pin "3") (pinfunction "SDA_3") (pintype "passive"))
      (node (ref "U3") (pin "13") (pinfunction "SD4_13") (pintype "passive"))
    )
    (net (code "25") (name "/SDA_06") (class "Default")
      (node (ref "R18") (pin "1") (pinfunction "1_1") (pintype "passive"))
      (node (ref "U12") (pin "3") (pinfunction "SDA_3") (pintype "passive"))
      (node (ref "U3") (pin "15") (pinfunction "SD5_15") (pintype "passive"))
    )
    (net (code "26") (name "/SDA_07") (class "Default")
      (node (ref "R20") (pin "1") (pinfunction "1_1") (pintype "passive"))
      (node (ref "U13") (pin "3") (pinfunction "SDA_3") (pintype "passive"))
      (node (ref "U3") (pin "17") (pinfunction "SD6_17") (pintype "passive"))
    )
    (net (code "27") (name "/SDA_08") (class "Default")
      (node (ref "R22") (pin "1") (pinfunction "1_1") (pintype "passive"))
      (node (ref "U14") (pin "3") (pinfunction "SDA_3") (pintype "passive"))
      (node (ref "U3") (pin "19") (pinfunction "SD7_19") (pintype "passive"))
    )
    (net (code "28") (name "/TXD0") (class "Default")
      (node (ref "U1") (pin "26") (pinfunction "TXD_26") (pintype "passive"))
      (node (ref "U2") (pin "31") (pinfunction "GPIO21/U0TXD_31") (pintype "passive"))
    )
    (net (code "29") (name "GND") (class "Default")
      (node (ref "C1") (pin "1") (pinfunction "1_1") (pintype "passive"))
      (node (ref "C10") (pin "1") (pinfunction "1_1") (pintype "passive"))
      (node (ref "C11") (pin "1") (pinfunction "1_1") (pintype "passive"))
      (node (ref "C12") (pin "1") (pinfunction "1_1") (pintype "passive"))
      (node (ref "C13") (pin "1") (pinfunction "1_1") (pintype "passive"))
      (node (ref "C14") (pin "1") (pinfunction "1_1") (pintype "passive"))
      (node (ref "C15") (pin "1") (pinfunction "1_1") (pintype "passive"))
      (node (ref "C16") (pin "1") (pinfunction "1_1") (pintype "passive"))
      (node (ref "C17") (pin "2") (pinfunction "2_2") (pintype "passive"))
      (node (ref "C18") (pin "2") (pinfunction "2_2") (pintype "passive"))
      (node (ref "C19") (pin "2") (pinfunction "2_2") (pintype "passive"))
      (node (ref "C2") (pin "1") (pinfunction "1_1") (pintype "passive"))
      (node (ref "C20") (pin "2") (pinfunction "2_2") (pintype "passive"))
      (node (ref "C21") (pin "1") (pinfunction "1_1") (pintype "passive"))
      (node (ref "C22") (pin "1") (pinfunction "1_1") (pintype "passive"))
      (node (ref "C23") (pin "1") (pinfunction "1_1") (pintype "passive"))
      (node (ref "C24") (pin "1") (pinfunction "1_1") (pintype "passive"))
      (node (ref "C25") (pin "1") (pinfunction "1_1") (pintype "passive"))
      (node (ref "C26") (pin "1") (pinfunction "1_1") (pintype "passive"))
      (node (ref "C27") (pin "1") (pinfunction "1_1") (pintype "passive"))
      (node (ref "C28") (pin "1") (pinfunction "1_1") (pintype "passive"))
      (node (ref "C3") (pin "1") (pinfunction "1_1") (pintype "passive"))
      (node (ref "C4") (pin "1") (pinfunction "1_1") (pintype "passive"))
      (node (ref "C5") (pin "1") (pinfunction "1_1") (pintype "passive"))
      (node (ref "C6") (pin "1") (pinfunction "1_1") (pintype "passive"))
      (node (ref "C7") (pin "1") (pinfunction "1_1") (pintype "passive"))
      (node (ref "C8") (pin "1") (pinfunction "1_1") (pintype "passive"))
      (node (ref "C9") (pin "1") (pinfunction "1_1") (pintype "passive"))
      (node (ref "D2") (pin "1") (pinfunction "A_1") (pintype "passive"))
      (node (ref "D2") (pin "A") (pinfunction "A_A") (pintype "passive"))
      (node (ref "D3") (pin "1") (pinfunction "A_1") (pintype "passive"))
      (node (ref "D3") (pin "A") (pinfunction "A_A") (pintype "passive"))
      (node (ref "D4") (pin "1") (pinfunction "A_1") (pintype "passive"))
      (node (ref "D4") (pin "A") (pinfunction "A_A") (pintype "passive"))
      (node (ref "D5") (pin "K") (pinfunction "K_K") (pintype "passive"))
      (node (ref "J1") (pin "A1B12") (pinfunction "GND_A1B12") (pintype "passive"))
      (node (ref "J1") (pin "B1A12") (pinfunction "GND_B1A12") (pintype "passive"))
      (node (ref "J1") (pin "SH") (pinfunction "SH_SH") (pintype "passive"))
      (node (ref "J10") (pin "3") (pinfunction "MNT_1_3") (pintype "passive"))
      (node (ref "J10") (pin "4") (pinfunction "MNT_2_4") (pintype "passive"))
      (node (ref "J11") (pin "3") (pinfunction "MNT_1_3") (pintype "passive"))
      (node (ref "J11") (pin "4") (pinfunction "MNT_2_4") (pintype "passive"))
      (node (ref "J2") (pin "2") (pinfunction "2_2") (pintype "passive"))
      (node (ref "J2") (pin "MP1") (pinfunction "MP1_MP1") (pintype "passive"))
      (node (ref "J2") (pin "MP2") (pinfunction "MP2_MP2") (pintype "passive"))
      (node (ref "J3") (pin "3") (pinfunction "MNT_1_3") (pintype "passive"))
      (node (ref "J3") (pin "4") (pinfunction "MNT_2_4") (pintype "passive"))
      (node (ref "J4") (pin "3") (pinfunction "MNT_1_3") (pintype "passive"))
      (node (ref "J4") (pin "4") (pinfunction "MNT_2_4") (pintype "passive"))
      (node (ref "J5") (pin "3") (pinfunction "MNT_1_3") (pintype "passive"))
      (node (ref "J5") (pin "4") (pinfunction "MNT_2_4") (pintype "passive"))
      (node (ref "J6") (pin "3") (pinfunction "MNT_1_3") (pintype "passive"))
      (node (ref "J6") (pin "4") (pinfunction "MNT_2_4") (pintype "passive"))
      (node (ref "J7") (pin "2") (pinfunction "2_2") (pintype "passive"))
      (node (ref "J7") (pin "MP1") (pinfunction "MP1_MP1") (pintype "passive"))
      (node (ref "J7") (pin "MP2") (pinfunction "MP2_MP2") (pintype "passive"))
      (node (ref "J8") (pin "3") (pinfunction "MNT_1_3") (pintype "passive"))
      (node (ref "J8") (pin "4") (pinfunction "MNT_2_4") (pintype "passive"))
      (node (ref "J9") (pin "3") (pinfunction "MNT_1_3") (pintype "passive"))
      (node (ref "J9") (pin "4") (pinfunction "MNT_2_4") (pintype "passive"))
      (node (ref "R32") (pin "1") (pinfunction "1_1") (pintype "passive"))
      (node (ref "R34") (pin "2") (pinfunction "2_2") (pintype "passive"))
      (node (ref "R36") (pin "2") (pinfunction "2_2") (pintype "passive"))
      (node (ref "R37") (pin "1") (pinfunction "1_1") (pintype "passive"))
      (node (ref "R4") (pin "1") (pinfunction "1_1") (pintype "passive"))
      (node (ref "R5") (pin "1") (pinfunction "1_1") (pintype "passive"))
      (node (ref "R6") (pin "1") (pinfunction "1_1") (pintype "passive"))
      (node (ref "SW1") (pin "4") (pinfunction "4_4") (pintype "passive"))
      (node (ref "SW1") (pin "5") (pinfunction "GROUND_5") (pintype "power_in"))
      (node (ref "SW2") (pin "4") (pinfunction "4_4") (pintype "passive"))
      (node (ref "SW2") (pin "5") (pinfunction "GROUND_5") (pintype "power_in"))
      (node (ref "U1") (pin "29") (pinfunction "GND_29") (pintype "passive"))
      (node (ref "U1") (pin "3") (pinfunction "GND_3") (pintype "passive"))
      (node (ref "U10") (pin "2") (pinfunction "VSS_2") (pintype "power_in"))
      (node (ref "U11") (pin "4") (pinfunction "IN/TRIG_4") (pintype "passive"))
      (node (ref "U11") (pin "8") (pinfunction "GND_8") (pintype "passive"))
      (node (ref "U12") (pin "4") (pinfunction "IN/TRIG_4") (pintype "passive"))
      (node (ref "U12") (pin "8") (pinfunction "GND_8") (pintype "passive"))
      (node (ref "U13") (pin "4") (pinfunction "IN/TRIG_4") (pintype "passive"))
      (node (ref "U13") (pin "8") (pinfunction "GND_8") (pintype "passive"))
      (node (ref "U14") (pin "4") (pinfunction "IN/TRIG_4") (pintype "passive"))
      (node (ref "U14") (pin "8") (pinfunction "GND_8") (pintype "passive"))
      (node (ref "U2") (pin "1") (pinfunction "GND_1") (pintype "passive"))
      (node (ref "U2") (pin "11") (pinfunction "GND_11") (pintype "passive"))
      (node (ref "U2") (pin "14") (pinfunction "GND_14") (pintype "passive"))
      (node (ref "U2") (pin "2") (pinfunction "GND_2") (pintype "passive"))
      (node (ref "U2") (pin "36") (pinfunction "GND_36") (pintype "passive"))
      (node (ref "U2") (pin "37") (pinfunction "GND_37") (pintype "passive"))
      (node (ref "U2") (pin "38") (pinfunction "GND_38") (pintype "passive"))
      (node (ref "U2") (pin "39") (pinfunction "GND_39") (pintype "passive"))
      (node (ref "U2") (pin "40") (pinfunction "GND_40") (pintype "passive"))
      (node (ref "U2") (pin "41") (pinfunction "GND_41") (pintype "passive"))
      (node (ref "U2") (pin "42") (pinfunction "GND_42") (pintype "passive"))
      (node (ref "U2") (pin "43") (pinfunction "GND_43") (pintype "passive"))
      (node (ref "U2") (pin "44") (pinfunction "GND_44") (pintype "passive"))
      (node (ref "U2") (pin "45") (pinfunction "GND_45") (pintype "passive"))
      (node (ref "U2") (pin "46") (pinfunction "GND_46") (pintype "passive"))
      (node (ref "U2") (pin "47") (pinfunction "GND_47") (pintype "passive"))
      (node (ref "U2") (pin "48") (pinfunction "GND_48") (pintype "passive"))
      (node (ref "U2") (pin "49") (pinfunction "GND_49") (pintype "passive"))
      (node (ref "U2") (pin "50") (pinfunction "GND_50") (pintype "passive"))
      (node (ref "U2") (pin "51") (pinfunction "GND_51") (pintype "passive"))
      (node (ref "U2") (pin "52") (pinfunction "GND_52") (pintype "passive"))
      (node (ref "U2") (pin "53") (pinfunction "GND_53") (pintype "passive"))
      (node (ref "U2") (pin "54") (pinfunction "GND_54") (pintype "passive"))
      (node (ref "U2") (pin "55") (pinfunction "GND_55") (pintype "passive"))
      (node (ref "U2") (pin "56") (pinfunction "GND_56") (pintype "passive"))
      (node (ref "U2") (pin "57") (pinfunction "GND_57") (pintype "passive"))
      (node (ref "U2") (pin "58") (pinfunction "GND_58") (pintype "passive"))
      (node (ref "U2") (pin "59") (pinfunction "GND_59") (pintype "passive"))
      (node (ref "U2") (pin "60") (pinfunction "GND_60") (pintype "passive"))
      (node (ref "U2") (pin "61") (pinfunction "GND_61") (pintype "passive"))
      (node (ref "U3") (pin "1") (pinfunction "A0_1") (pintype "passive"))
      (node (ref "U3") (pin "12") (pinfunction "GND_12") (pintype "passive"))
      (node (ref "U3") (pin "2") (pinfunction "A1_2") (pintype "passive"))
      (node (ref "U3") (pin "21") (pinfunction "A2_21") (pintype "passive"))
      (node (ref "U4") (pin "10") (pinfunction "PFM/PWM_10") (pintype "passive"))
      (node (ref "U4") (pin "2") (pinfunction "PGND_2") (pintype "passive"))
      (node (ref "U4") (pin "9") (pinfunction "GND_9") (pintype "passive"))
      (node (ref "U5") (pin "4") (pinfunction "IN/TRIG_4") (pintype "passive"))
      (node (ref "U5") (pin "8") (pinfunction "GND_8") (pintype "passive"))
      (node (ref "U6") (pin "4") (pinfunction "IN/TRIG_4") (pintype "passive"))
      (node (ref "U6") (pin "8") (pinfunction "GND_8") (pintype "passive"))
      (node (ref "U7") (pin "4") (pinfunction "IN/TRIG_4") (pintype "passive"))
      (node (ref "U7") (pin "8") (pinfunction "GND_8") (pintype "passive"))
      (node (ref "U8") (pin "4") (pinfunction "IN/TRIG_4") (pintype "passive"))
      (node (ref "U8") (pin "8") (pinfunction "GND_8") (pintype "passive"))
      (node (ref "U9") (pin "2") (pinfunction "VSS_2") (pintype "power_in"))
    )
    (net (code "30") (name "Net-(D5-PadA)") (class "Default")
      (node (ref "D5") (pin "A") (pinfunction "A_A") (pintype "passive"))
      (node (ref "R30") (pin "1") (pinfunction "1_1") (pintype "passive"))
    )
    (net (code "31") (name "Net-(D6-C)") (class "Default")
      (node (ref "D6") (pin "1") (pinfunction "C_1") (pintype "passive"))
      (node (ref "D7") (pin "1") (pinfunction "C_1") (pintype "passive"))
      (node (ref "Q3") (pin "3") (pinfunction "D_3") (pintype "passive"))
    )
    (net (code "32") (name "Net-(D8-PadA)") (class "Default")
      (node (ref "D8") (pin "A") (pinfunction "A_A") (pintype "passive"))
      (node (ref "R33") (pin "2") (pinfunction "2_2") (pintype "passive"))
    )
    (net (code "33") (name "Net-(D9-PadA)") (class "Default")
      (node (ref "D9") (pin "A") (pinfunction "A_A") (pintype "passive"))
      (node (ref "R35") (pin "2") (pinfunction "2_2") (pintype "passive"))
    )
    (net (code "34") (name "Net-(J1-CC1)") (class "Default")
      (node (ref "J1") (pin "A5") (pinfunction "CC1_A5") (pintype "passive"))
      (node (ref "R6") (pin "2") (pinfunction "2_2") (pintype "passive"))
    )
    (net (code "35") (name "Net-(J1-CC2)") (class "Default")
      (node (ref "J1") (pin "B5") (pinfunction "CC2_B5") (pintype "passive"))
      (node (ref "R5") (pin "2") (pinfunction "2_2") (pintype "passive"))
    )
    (net (code "36") (name "Net-(Q1-B)") (class "Default")
      (node (ref "Q1") (pin "1") (pinfunction "B_1") (pintype "passive"))
      (node (ref "R23") (pin "1") (pinfunction "1_1") (pintype "passive"))
    )
    (net (code "37") (name "Net-(Q2-B)") (class "Default")
      (node (ref "Q2") (pin "1") (pinfunction "B_1") (pintype "passive"))
      (node (ref "R25") (pin "1") (pinfunction "1_1") (pintype "passive"))
    )
    (net (code "38") (name "Net-(U1-VBUS)") (class "Default")
      (node (ref "R3") (pin "1") (pinfunction "1_1") (pintype "passive"))
      (node (ref "R4") (pin "2") (pinfunction "2_2") (pintype "passive"))
      (node (ref "U1") (pin "8") (pinfunction "VBUS_8") (pintype "passive"))
    )
    (net (code "39") (name "Net-(U1-~{RST})") (class "Default")
      (node (ref "R2") (pin "1") (pinfunction "1_1") (pintype "passive"))
      (node (ref "U1") (pin "9") (pinfunction "~{RST}_9") (pintype "passive"))
    )
    (net (code "40") (name "Net-(U3-~{RESET})") (class "Default")
      (node (ref "R24") (pin "1") (pinfunction "1_1") (pintype "passive"))
      (node (ref "U3") (pin "3") (pinfunction "~{RESET}_3") (pintype "passive"))
    )
    (net (code "41") (name "Net-(U4-FB)") (class "Default")
      (node (ref "R31") (pin "1") (pinfunction "1_1") (pintype "passive"))
      (node (ref "R32") (pin "2") (pinfunction "2_2") (pintype "passive"))
      (node (ref "U4") (pin "11") (pinfunction "FB_11") (pintype "passive"))
    )
    (net (code "42") (name "Net-(U4-L1)") (class "Default")
      (node (ref "L1") (pin "1") (pinfunction "1_1") (pintype "passive"))
      (node (ref "U4") (pin "3") (pinfunction "L1_3") (pintype "passive"))
    )
    (net (code "43") (name "Net-(U4-L2)") (class "Default")
      (node (ref "L1") (pin "2") (pinfunction "2_2") (pintype "passive"))
      (node (ref "U4") (pin "1") (pinfunction "L2_1") (pintype "passive"))
    )
    (net (code "44") (name "Net-(U5-OUT+)") (class "Default")
      (node (ref "J3") (pin "1") (pinfunction "1_1") (pintype "passive"))
      (node (ref "U5") (pin "7") (pinfunction "OUT+_7") (pintype "passive"))
    )
    (net (code "45") (name "Net-(U5-OUT-)") (class "Default")
      (node (ref "J3") (pin "2") (pinfunction "2_2") (pintype "passive"))
      (node (ref "U5") (pin "9") (pinfunction "OUT-_9") (pintype "passive"))
    )
    (net (code "46") (name "Net-(U5-REG)") (class "Default")
      (node (ref "C10") (pin "2") (pinfunction "2_2") (pintype "passive"))
      (node (ref "U5") (pin "1") (pinfunction "REG_1") (pintype "passive"))
    )
    (net (code "47") (name "Net-(U6-OUT+)") (class "Default")
      (node (ref "J4") (pin "1") (pinfunction "1_1") (pintype "passive"))
      (node (ref "U6") (pin "7") (pinfunction "OUT+_7") (pintype "passive"))
    )
    (net (code "48") (name "Net-(U6-OUT-)") (class "Default")
      (node (ref "J4") (pin "2") (pinfunction "2_2") (pintype "passive"))
      (node (ref "U6") (pin "9") (pinfunction "OUT-_9") (pintype "passive"))
    )
    (net (code "49") (name "Net-(U6-REG)") (class "Default")
      (node (ref "C12") (pin "2") (pinfunction "2_2") (pintype "passive"))
      (node (ref "U6") (pin "1") (pinfunction "REG_1") (pintype "passive"))
    )
    (net (code "50") (name "Net-(U7-OUT+)") (class "Default")
      (node (ref "J5") (pin "1") (pinfunction "1_1") (pintype "passive"))
      (node (ref "U7") (pin "7") (pinfunction "OUT+_7") (pintype "passive"))
    )
    (net (code "51") (name "Net-(U7-OUT-)") (class "Default")
      (node (ref "J5") (pin "2") (pinfunction "2_2") (pintype "passive"))
      (node (ref "U7") (pin "9") (pinfunction "OUT-_9") (pintype "passive"))
    )
    (net (code "52") (name "Net-(U7-REG)") (class "Default")
      (node (ref "C14") (pin "2") (pinfunction "2_2") (pintype "passive"))
      (node (ref "U7") (pin "1") (pinfunction "REG_1") (pintype "passive"))
    )
    (net (code "53") (name "Net-(U8-OUT+)") (class "Default")
      (node (ref "J6") (pin "1") (pinfunction "1_1") (pintype "passive"))
      (node (ref "U8") (pin "7") (pinfunction "OUT+_7") (pintype "passive"))
    )
    (net (code "54") (name "Net-(U8-OUT-)") (class "Default")
      (node (ref "J6") (pin "2") (pinfunction "2_2") (pintype "passive"))
      (node (ref "U8") (pin "9") (pinfunction "OUT-_9") (pintype "passive"))
    )
    (net (code "55") (name "Net-(U8-REG)") (class "Default")
      (node (ref "C16") (pin "2") (pinfunction "2_2") (pintype "passive"))
      (node (ref "U8") (pin "1") (pinfunction "REG_1") (pintype "passive"))
    )
    (net (code "56") (name "Net-(U9-PROG)") (class "Default")
      (node (ref "R34") (pin "1") (pinfunction "1_1") (pintype "passive"))
      (node (ref "U9") (pin "5") (pinfunction "PROG_5") (pintype "passive"))
    )
    (net (code "57") (name "Net-(U9-STAT)") (class "Default")
      (node (ref "D8") (pin "K") (pinfunction "K_K") (pintype "passive"))
      (node (ref "U9") (pin "1") (pinfunction "STAT_1") (pintype "passive"))
    )
    (net (code "58") (name "Net-(U10-PROG)") (class "Default")
      (node (ref "R36") (pin "1") (pinfunction "1_1") (pintype "passive"))
      (node (ref "U10") (pin "5") (pinfunction "PROG_5") (pintype "passive"))
    )
    (net (code "59") (name "Net-(U10-STAT)") (class "Default")
      (node (ref "D9") (pin "K") (pinfunction "K_K") (pintype "passive"))
      (node (ref "U10") (pin "1") (pinfunction "STAT_1") (pintype "passive"))
    )
    (net (code "60") (name "Net-(U11-OUT+)") (class "Default")
      (node (ref "J8") (pin "1") (pinfunction "1_1") (pintype "passive"))
      (node (ref "U11") (pin "7") (pinfunction "OUT+_7") (pintype "passive"))
    )
    (net (code "61") (name "Net-(U11-OUT-)") (class "Default")
      (node (ref "J8") (pin "2") (pinfunction "2_2") (pintype "passive"))
      (node (ref "U11") (pin "9") (pinfunction "OUT-_9") (pintype "passive"))
    )
    (net (code "62") (name "Net-(U11-REG)") (class "Default")
      (node (ref "C22") (pin "2") (pinfunction "2_2") (pintype "passive"))
      (node (ref "U11") (pin "1") (pinfunction "REG_1") (pintype "passive"))
    )
    (net (code "63") (name "Net-(U12-OUT+)") (class "Default")
      (node (ref "J9") (pin "1") (pinfunction "1_1") (pintype "passive"))
      (node (ref "U12") (pin "7") (pinfunction "OUT+_7") (pintype "passive"))
    )
    (net (code "64") (name "Net-(U12-OUT-)") (class "Default")
      (node (ref "J9") (pin "2") (pinfunction "2_2") (pintype "passive"))
      (node (ref "U12") (pin "9") (pinfunction "OUT-_9") (pintype "passive"))
    )
    (net (code "65") (name "Net-(U12-REG)") (class "Default")
      (node (ref "C24") (pin "2") (pinfunction "2_2") (pintype "passive"))
      (node (ref "U12") (pin "1") (pinfunction "REG_1") (pintype "passive"))
    )
    (net (code "66") (name "Net-(U13-OUT+)") (class "Default")
      (node (ref "J10") (pin "1") (pinfunction "1_1") (pintype "passive"))
      (node (ref "U13") (pin "7") (pinfunction "OUT+_7") (pintype "passive"))
    )
    (net (code "67") (name "Net-(U13-OUT-)") (class "Default")
      (node (ref "J10") (pin "2") (pinfunction "2_2") (pintype "passive"))
      (node (ref "U13") (pin "9") (pinfunction "OUT-_9") (pintype "passive"))
    )
    (net (code "68") (name "Net-(U13-REG)") (class "Default")
      (node (ref "C26") (pin "2") (pinfunction "2_2") (pintype "passive"))
      (node (ref "U13") (pin "1") (pinfunction "REG_1") (pintype "passive"))
    )
    (net (code "69") (name "Net-(U14-OUT+)") (class "Default")
      (node (ref "J11") (pin "1") (pinfunction "1_1") (pintype "passive"))
      (node (ref "U14") (pin "7") (pinfunction "OUT+_7") (pintype "passive"))
    )
    (net (code "70") (name "Net-(U14-OUT-)") (class "Default")
      (node (ref "J11") (pin "2") (pinfunction "2_2") (pintype "passive"))
      (node (ref "U14") (pin "9") (pinfunction "OUT-_9") (pintype "passive"))
    )
    (net (code "71") (name "Net-(U14-REG)") (class "Default")
      (node (ref "C28") (pin "2") (pinfunction "2_2") (pintype "passive"))
      (node (ref "U14") (pin "1") (pinfunction "REG_1") (pintype "passive"))
    )
    (net (code "72") (name "SELECTED") (class "Default")
      (node (ref "C6") (pin "2") (pinfunction "2_2") (pintype "passive"))
      (node (ref "D10") (pin "1") (pinfunction "C_1") (pintype "passive"))
      (node (ref "Q3") (pin "2") (pinfunction "S_2") (pintype "passive"))
      (node (ref "U4") (pin "4") (pinfunction "VIN_4") (pintype "passive"))
      (node (ref "U4") (pin "5") (pinfunction "VIN_5") (pintype "passive"))
      (node (ref "U4") (pin "6") (pinfunction "VIN_6") (pintype "passive"))
      (node (ref "U4") (pin "7") (pinfunction "VINA_7") (pintype "passive"))
      (node (ref "U4") (pin "8") (pinfunction "EN_8") (pintype "passive"))
    )
    (net (code "73") (name "VCC_3V3") (class "Default")
      (node (ref "C11") (pin "2") (pinfunction "2_2") (pintype "passive"))
      (node (ref "C13") (pin "2") (pinfunction "2_2") (pintype "passive"))
      (node (ref "C15") (pin "2") (pinfunction "2_2") (pintype "passive"))
      (node (ref "C2") (pin "2") (pinfunction "2_2") (pintype "passive"))
      (node (ref "C21") (pin "2") (pinfunction "2_2") (pintype "passive"))
      (node (ref "C23") (pin "2") (pinfunction "2_2") (pintype "passive"))
      (node (ref "C25") (pin "2") (pinfunction "2_2") (pintype "passive"))
      (node (ref "C27") (pin "2") (pinfunction "2_2") (pintype "passive"))
      (node (ref "C3") (pin "2") (pinfunction "2_2") (pintype "passive"))
      (node (ref "C4") (pin "2") (pinfunction "2_2") (pintype "passive"))
      (node (ref "C5") (pin "2") (pinfunction "2_2") (pintype "passive"))
      (node (ref "C7") (pin "2") (pinfunction "2_2") (pintype "passive"))
      (node (ref "C8") (pin "2") (pinfunction "2_2") (pintype "passive"))
      (node (ref "C9") (pin "2") (pinfunction "2_2") (pintype "passive"))
      (node (ref "R1") (pin "2") (pinfunction "2_2") (pintype "passive"))
      (node (ref "R10") (pin "2") (pinfunction "2_2") (pintype "passive"))
      (node (ref "R11") (pin "2") (pinfunction "2_2") (pintype "passive"))
      (node (ref "R12") (pin "2") (pinfunction "2_2") (pintype "passive"))
      (node (ref "R13") (pin "2") (pinfunction "2_2") (pintype "passive"))
      (node (ref "R14") (pin "2") (pinfunction "2_2") (pintype "passive"))
      (node (ref "R15") (pin "2") (pinfunction "2_2") (pintype "passive"))
      (node (ref "R16") (pin "2") (pinfunction "2_2") (pintype "passive"))
      (node (ref "R17") (pin "2") (pinfunction "2_2") (pintype "passive"))
      (node (ref "R18") (pin "2") (pinfunction "2_2") (pintype "passive"))
      (node (ref "R19") (pin "2") (pinfunction "2_2") (pintype "passive"))
      (node (ref "R2") (pin "2") (pinfunction "2_2") (pintype "passive"))
      (node (ref "R20") (pin "2") (pinfunction "2_2") (pintype "passive"))
      (node (ref "R21") (pin "2") (pinfunction "2_2") (pintype "passive"))
      (node (ref "R22") (pin "2") (pinfunction "2_2") (pintype "passive"))
      (node (ref "R24") (pin "2") (pinfunction "2_2") (pintype "passive"))
      (node (ref "R26") (pin "2") (pinfunction "2_2") (pintype "passive"))
      (node (ref "R27") (pin "2") (pinfunction "2_2") (pintype "passive"))
      (node (ref "R28") (pin "2") (pinfunction "2_2") (pintype "passive"))
      (node (ref "R29") (pin "2") (pinfunction "2_2") (pintype "passive"))
      (node (ref "R30") (pin "2") (pinfunction "2_2") (pintype "passive"))
      (node (ref "R31") (pin "2") (pinfunction "2_2") (pintype "passive"))
      (node (ref "R7") (pin "2") (pinfunction "2_2") (pintype "passive"))
      (node (ref "R8") (pin "2") (pinfunction "2_2") (pintype "passive"))
      (node (ref "R9") (pin "2") (pinfunction "2_2") (pintype "passive"))
      (node (ref "U1") (pin "6") (pinfunction "VDD_6") (pintype "passive"))
      (node (ref "U1") (pin "7") (pinfunction "VREGIN_7") (pintype "passive"))
      (node (ref "U11") (pin "10") (pinfunction "VDD_10") (pintype "passive"))
      (node (ref "U11") (pin "5") (pinfunction "EN_5") (pintype "passive"))
      (node (ref "U11") (pin "6") (pinfunction "VDD/NC_6") (pintype "passive"))
      (node (ref "U12") (pin "10") (pinfunction "VDD_10") (pintype "passive"))
      (node (ref "U12") (pin "5") (pinfunction "EN_5") (pintype "passive"))
      (node (ref "U12") (pin "6") (pinfunction "VDD/NC_6") (pintype "passive"))
      (node (ref "U13") (pin "10") (pinfunction "VDD_10") (pintype "passive"))
      (node (ref "U13") (pin "5") (pinfunction "EN_5") (pintype "passive"))
      (node (ref "U13") (pin "6") (pinfunction "VDD/NC_6") (pintype "passive"))
      (node (ref "U14") (pin "10") (pinfunction "VDD_10") (pintype "passive"))
      (node (ref "U14") (pin "5") (pinfunction "EN_5") (pintype "passive"))
      (node (ref "U14") (pin "6") (pinfunction "VDD/NC_6") (pintype "passive"))
      (node (ref "U2") (pin "3") (pinfunction "3V3_3") (pintype "passive"))
      (node (ref "U3") (pin "24") (pinfunction "VCC_24") (pintype "passive"))
      (node (ref "U4") (pin "12") (pinfunction "VOUT_12") (pintype "passive"))
      (node (ref "U4") (pin "13") (pinfunction "VOUT_13") (pintype "passive"))
      (node (ref "U4") (pin "14") (pinfunction "VOUT_14") (pintype "passive"))
      (node (ref "U5") (pin "10") (pinfunction "VDD_10") (pintype "passive"))
      (node (ref "U5") (pin "5") (pinfunction "EN_5") (pintype "passive"))
      (node (ref "U5") (pin "6") (pinfunction "VDD/NC_6") (pintype "passive"))
      (node (ref "U6") (pin "10") (pinfunction "VDD_10") (pintype "passive"))
      (node (ref "U6") (pin "5") (pinfunction "EN_5") (pintype "passive"))
      (node (ref "U6") (pin "6") (pinfunction "VDD/NC_6") (pintype "passive"))
      (node (ref "U7") (pin "10") (pinfunction "VDD_10") (pintype "passive"))
      (node (ref "U7") (pin "5") (pinfunction "EN_5") (pintype "passive"))
      (node (ref "U7") (pin "6") (pinfunction "VDD/NC_6") (pintype "passive"))
      (node (ref "U8") (pin "10") (pinfunction "VDD_10") (pintype "passive"))
      (node (ref "U8") (pin "5") (pinfunction "EN_5") (pintype "passive"))
      (node (ref "U8") (pin "6") (pinfunction "VDD/NC_6") (pintype "passive"))
    )
    (net (code "74") (name "VCC_BATT1") (class "Default")
      (node (ref "C17") (pin "1") (pinfunction "1_1") (pintype "passive"))
      (node (ref "D6") (pin "2") (pinfunction "A_2") (pintype "passive"))
      (node (ref "J2") (pin "1") (pinfunction "1_1") (pintype "passive"))
      (node (ref "U9") (pin "3") (pinfunction "VBAT_3") (pintype "power_in"))
    )
    (net (code "75") (name "VCC_BATT2") (class "Default")
      (node (ref "C18") (pin "1") (pinfunction "1_1") (pintype "passive"))
      (node (ref "D7") (pin "2") (pinfunction "A_2") (pintype "passive"))
      (node (ref "J7") (pin "1") (pinfunction "1_1") (pintype "passive"))
      (node (ref "U10") (pin "3") (pinfunction "VBAT_3") (pintype "power_in"))
    )
    (net (code "76") (name "VCC_USB") (class "Default")
      (node (ref "C19") (pin "1") (pinfunction "1_1") (pintype "passive"))
      (node (ref "C20") (pin "1") (pinfunction "1_1") (pintype "passive"))
      (node (ref "D10") (pin "2") (pinfunction "A_2") (pintype "passive"))
      (node (ref "D4") (pin "2") (pinfunction "K_2") (pintype "passive"))
      (node (ref "D4") (pin "K") (pinfunction "K_K") (pintype "passive"))
      (node (ref "J1") (pin "A4B9") (pinfunction "VBUS_A4B9") (pintype "passive"))
      (node (ref "J1") (pin "B4A9") (pinfunction "VBUS_B4A9") (pintype "passive"))
      (node (ref "Q3") (pin "1") (pinfunction "G_1") (pintype "passive"))
      (node (ref "R3") (pin "2") (pinfunction "2_2") (pintype "passive"))
      (node (ref "R33") (pin "1") (pinfunction "1_1") (pintype "passive"))
      (node (ref "R35") (pin "1") (pinfunction "1_1") (pintype "passive"))
      (node (ref "R37") (pin "2") (pinfunction "2_2") (pintype "passive"))
      (node (ref "U10") (pin "4") (pinfunction "VDD_4") (pintype "power_in"))
      (node (ref "U9") (pin "4") (pinfunction "VDD_4") (pintype "power_in"))
    )
    (net (code "77") (name "unconnected-(J1-SBU1-PadA8)") (class "Default")
      (node (ref "J1") (pin "A8") (pinfunction "SBU1_A8") (pintype "passive+no_connect"))
    )
    (net (code "78") (name "unconnected-(J1-SBU2-PadB8)") (class "Default")
      (node (ref "J1") (pin "B8") (pinfunction "SBU2_B8") (pintype "passive+no_connect"))
    )
    (net (code "79") (name "unconnected-(SW1-Pad1)") (class "Default")
      (node (ref "SW1") (pin "1") (pinfunction "1_1") (pintype "passive+no_connect"))
    )
    (net (code "80") (name "unconnected-(SW1-Pad3)") (class "Default")
      (node (ref "SW1") (pin "3") (pinfunction "3_3") (pintype "passive+no_connect"))
    )
    (net (code "81") (name "unconnected-(SW2-Pad1)") (class "Default")
      (node (ref "SW2") (pin "1") (pinfunction "1_1") (pintype "passive+no_connect"))
    )
    (net (code "82") (name "unconnected-(SW2-Pad3)") (class "Default")
      (node (ref "SW2") (pin "3") (pinfunction "3_3") (pintype "passive+no_connect"))
    )
    (net (code "83") (name "unconnected-(U1-CHR0-Pad15)") (class "Default")
      (node (ref "U1") (pin "15") (pinfunction "CHR0_15") (pintype "passive+no_connect"))
    )
    (net (code "84") (name "unconnected-(U1-CHR1-Pad14)") (class "Default")
      (node (ref "U1") (pin "14") (pinfunction "CHR1_14") (pintype "passive+no_connect"))
    )
    (net (code "85") (name "unconnected-(U1-CHREN-Pad13)") (class "Default")
      (node (ref "U1") (pin "13") (pinfunction "CHREN_13") (pintype "passive+no_connect"))
    )
    (net (code "86") (name "unconnected-(U1-CTS-Pad23)") (class "Default")
      (node (ref "U1") (pin "23") (pinfunction "CTS_23") (pintype "passive+no_connect"))
    )
    (net (code "87") (name "unconnected-(U1-DCD-Pad1)") (class "Default")
      (node (ref "U1") (pin "1") (pinfunction "DCD_1") (pintype "passive+no_connect"))
    )
    (net (code "88") (name "unconnected-(U1-DSR-Pad27)") (class "Default")
      (node (ref "U1") (pin "27") (pinfunction "DSR_27") (pintype "passive+no_connect"))
    )
    (net (code "89") (name "unconnected-(U1-GPIO.0{slash}TXT-Pad19)") (class "Default")
      (node (ref "U1") (pin "19") (pinfunction "GPIO.0/TXT_19") (pintype "passive+no_connect"))
    )
    (net (code "90") (name "unconnected-(U1-GPIO.1{slash}RXT-Pad18)") (class "Default")
      (node (ref "U1") (pin "18") (pinfunction "GPIO.1/RXT_18") (pintype "passive+no_connect"))
    )
    (net (code "91") (name "unconnected-(U1-GPIO.2{slash}RS485-Pad17)") (class "Default")
      (node (ref "U1") (pin "17") (pinfunction "GPIO.2/RS485_17") (pintype "passive+no_connect"))
    )
    (net (code "92") (name "unconnected-(U1-GPIO.3{slash}WAKEUP-Pad16)") (class "Default")
      (node (ref "U1") (pin "16") (pinfunction "GPIO.3/WAKEUP_16") (pintype "passive+no_connect"))
    )
    (net (code "93") (name "unconnected-(U1-GPIO.4-Pad22)") (class "Default")
      (node (ref "U1") (pin "22") (pinfunction "GPIO.4_22") (pintype "passive+no_connect"))
    )
    (net (code "94") (name "unconnected-(U1-GPIO.5-Pad21)") (class "Default")
      (node (ref "U1") (pin "21") (pinfunction "GPIO.5_21") (pintype "passive+no_connect"))
    )
    (net (code "95") (name "unconnected-(U1-GPIO.6-Pad20)") (class "Default")
      (node (ref "U1") (pin "20") (pinfunction "GPIO.6_20") (pintype "passive+no_connect"))
    )
    (net (code "96") (name "unconnected-(U1-NC-Pad10)") (class "Default")
      (node (ref "U1") (pin "10") (pinfunction "NC_10") (pintype "passive+no_connect"))
    )
    (net (code "97") (name "unconnected-(U1-SUSPEND-Pad12)") (class "Default")
      (node (ref "U1") (pin "12") (pinfunction "SUSPEND_12") (pintype "passive+no_connect"))
    )
    (net (code "98") (name "unconnected-(U1-~{RI}{slash}CLK-Pad2)") (class "Default")
      (node (ref "U1") (pin "2") (pinfunction "~{RI}/CLK_2") (pintype "passive+no_connect"))
    )
    (net (code "99") (name "unconnected-(U1-~{SUSPEND}-Pad11)") (class "Default")
      (node (ref "U1") (pin "11") (pinfunction "~{SUSPEND}_11") (pintype "passive+no_connect"))
    )
    (net (code "100") (name "unconnected-(U2-GPIO0{slash}ADC1_CH0{slash}XTAL_32K_P-Pad12)") (class "Default")
      (node (ref "U2") (pin "12") (pinfunction "GPIO0/ADC1_CH0/XTAL_32K_P_12") (pintype "passive+no_connect"))
    )
    (net (code "101") (name "unconnected-(U2-GPIO1{slash}ADC1_CH1{slash}XTAL_32K_N-Pad13)") (class "Default")
      (node (ref "U2") (pin "13") (pinfunction "GPIO1/ADC1_CH1/XTAL_32K_N_13") (pintype "passive+no_connect"))
    )
    (net (code "102") (name "unconnected-(U2-GPIO3{slash}ADC1_CH3-Pad6)") (class "Default")
      (node (ref "U2") (pin "6") (pinfunction "GPIO3/ADC1_CH3_6") (pintype "passive+no_connect"))
    )
    (net (code "103") (name "unconnected-(U2-GPIO4{slash}ADC1_CH4{slash}FSPIHD{slash}MTMS-Pad18)") (class "Default")
      (node (ref "U2") (pin "18") (pinfunction "GPIO4/ADC1_CH4/FSPIHD/MTMS_18") (pintype "passive+no_connect"))
    )
    (net (code "104") (name "unconnected-(U2-GPIO5{slash}ADC2_CH0{slash}FSPIWP{slash}MTDI-Pad19)") (class "Default")
      (node (ref "U2") (pin "19") (pinfunction "GPIO5/ADC2_CH0/FSPIWP/MTDI_19") (pintype "passive+no_connect"))
    )
    (net (code "105") (name "unconnected-(U2-GPIO10{slash}FSPICS0-Pad16)") (class "Default")
      (node (ref "U2") (pin "16") (pinfunction "GPIO10/FSPICS0_16") (pintype "passive+no_connect"))
    )
    (net (code "106") (name "unconnected-(U2-GPIO18{slash}USB_D--Pad26)") (class "Default")
      (node (ref "U2") (pin "26") (pinfunction "GPIO18/USB_D-_26") (pintype "passive+no_connect"))
    )
    (net (code "107") (name "unconnected-(U2-GPIO19{slash}USB_D+-Pad27)") (class "Default")
      (node (ref "U2") (pin "27") (pinfunction "GPIO19/USB_D+_27") (pintype "passive+no_connect"))
    )
    (net (code "108") (name "unconnected-(U2-NC-Pad4)") (class "Default")
      (node (ref "U2") (pin "4") (pinfunction "NC_4") (pintype "passive+no_connect"))
    )
    (net (code "109") (name "unconnected-(U2-NC-Pad7)") (class "Default")
      (node (ref "U2") (pin "7") (pinfunction "NC_7") (pintype "passive+no_connect"))
    )
    (net (code "110") (name "unconnected-(U2-NC-Pad9)") (class "Default")
      (node (ref "U2") (pin "9") (pinfunction "NC_9") (pintype "passive+no_connect"))
    )
    (net (code "111") (name "unconnected-(U2-NC-Pad10)") (class "Default")
      (node (ref "U2") (pin "10") (pinfunction "NC_10") (pintype "passive+no_connect"))
    )
    (net (code "112") (name "unconnected-(U2-NC-Pad15)") (class "Default")
      (node (ref "U2") (pin "15") (pinfunction "NC_15") (pintype "passive+no_connect"))
    )
    (net (code "113") (name "unconnected-(U2-NC-Pad17)") (class "Default")
      (node (ref "U2") (pin "17") (pinfunction "NC_17") (pintype "passive+no_connect"))
    )
    (net (code "114") (name "unconnected-(U2-NC-Pad24)") (class "Default")
      (node (ref "U2") (pin "24") (pinfunction "NC_24") (pintype "passive+no_connect"))
    )
    (net (code "115") (name "unconnected-(U2-NC-Pad25)") (class "Default")
      (node (ref "U2") (pin "25") (pinfunction "NC_25") (pintype "passive+no_connect"))
    )
    (net (code "116") (name "unconnected-(U2-NC-Pad28)") (class "Default")
      (node (ref "U2") (pin "28") (pinfunction "NC_28") (pintype "passive+no_connect"))
    )
    (net (code "117") (name "unconnected-(U2-NC-Pad29)") (class "Default")
      (node (ref "U2") (pin "29") (pinfunction "NC_29") (pintype "passive+no_connect"))
    )
    (net (code "118") (name "unconnected-(U2-NC-Pad32)") (class "Default")
      (node (ref "U2") (pin "32") (pinfunction "NC_32") (pintype "passive+no_connect"))
    )
    (net (code "119") (name "unconnected-(U2-NC-Pad33)") (class "Default")
      (node (ref "U2") (pin "33") (pinfunction "NC_33") (pintype "passive+no_connect"))
    )
    (net (code "120") (name "unconnected-(U2-NC-Pad34)") (class "Default")
      (node (ref "U2") (pin "34") (pinfunction "NC_34") (pintype "passive+no_connect"))
    )
    (net (code "121") (name "unconnected-(U2-NC-Pad35)") (class "Default")
      (node (ref "U2") (pin "35") (pinfunction "NC_35") (pintype "passive+no_connect"))
    )
  )
)
